# pi3_hat.net
KiCad netlist of a schematic drawn in EAGLE
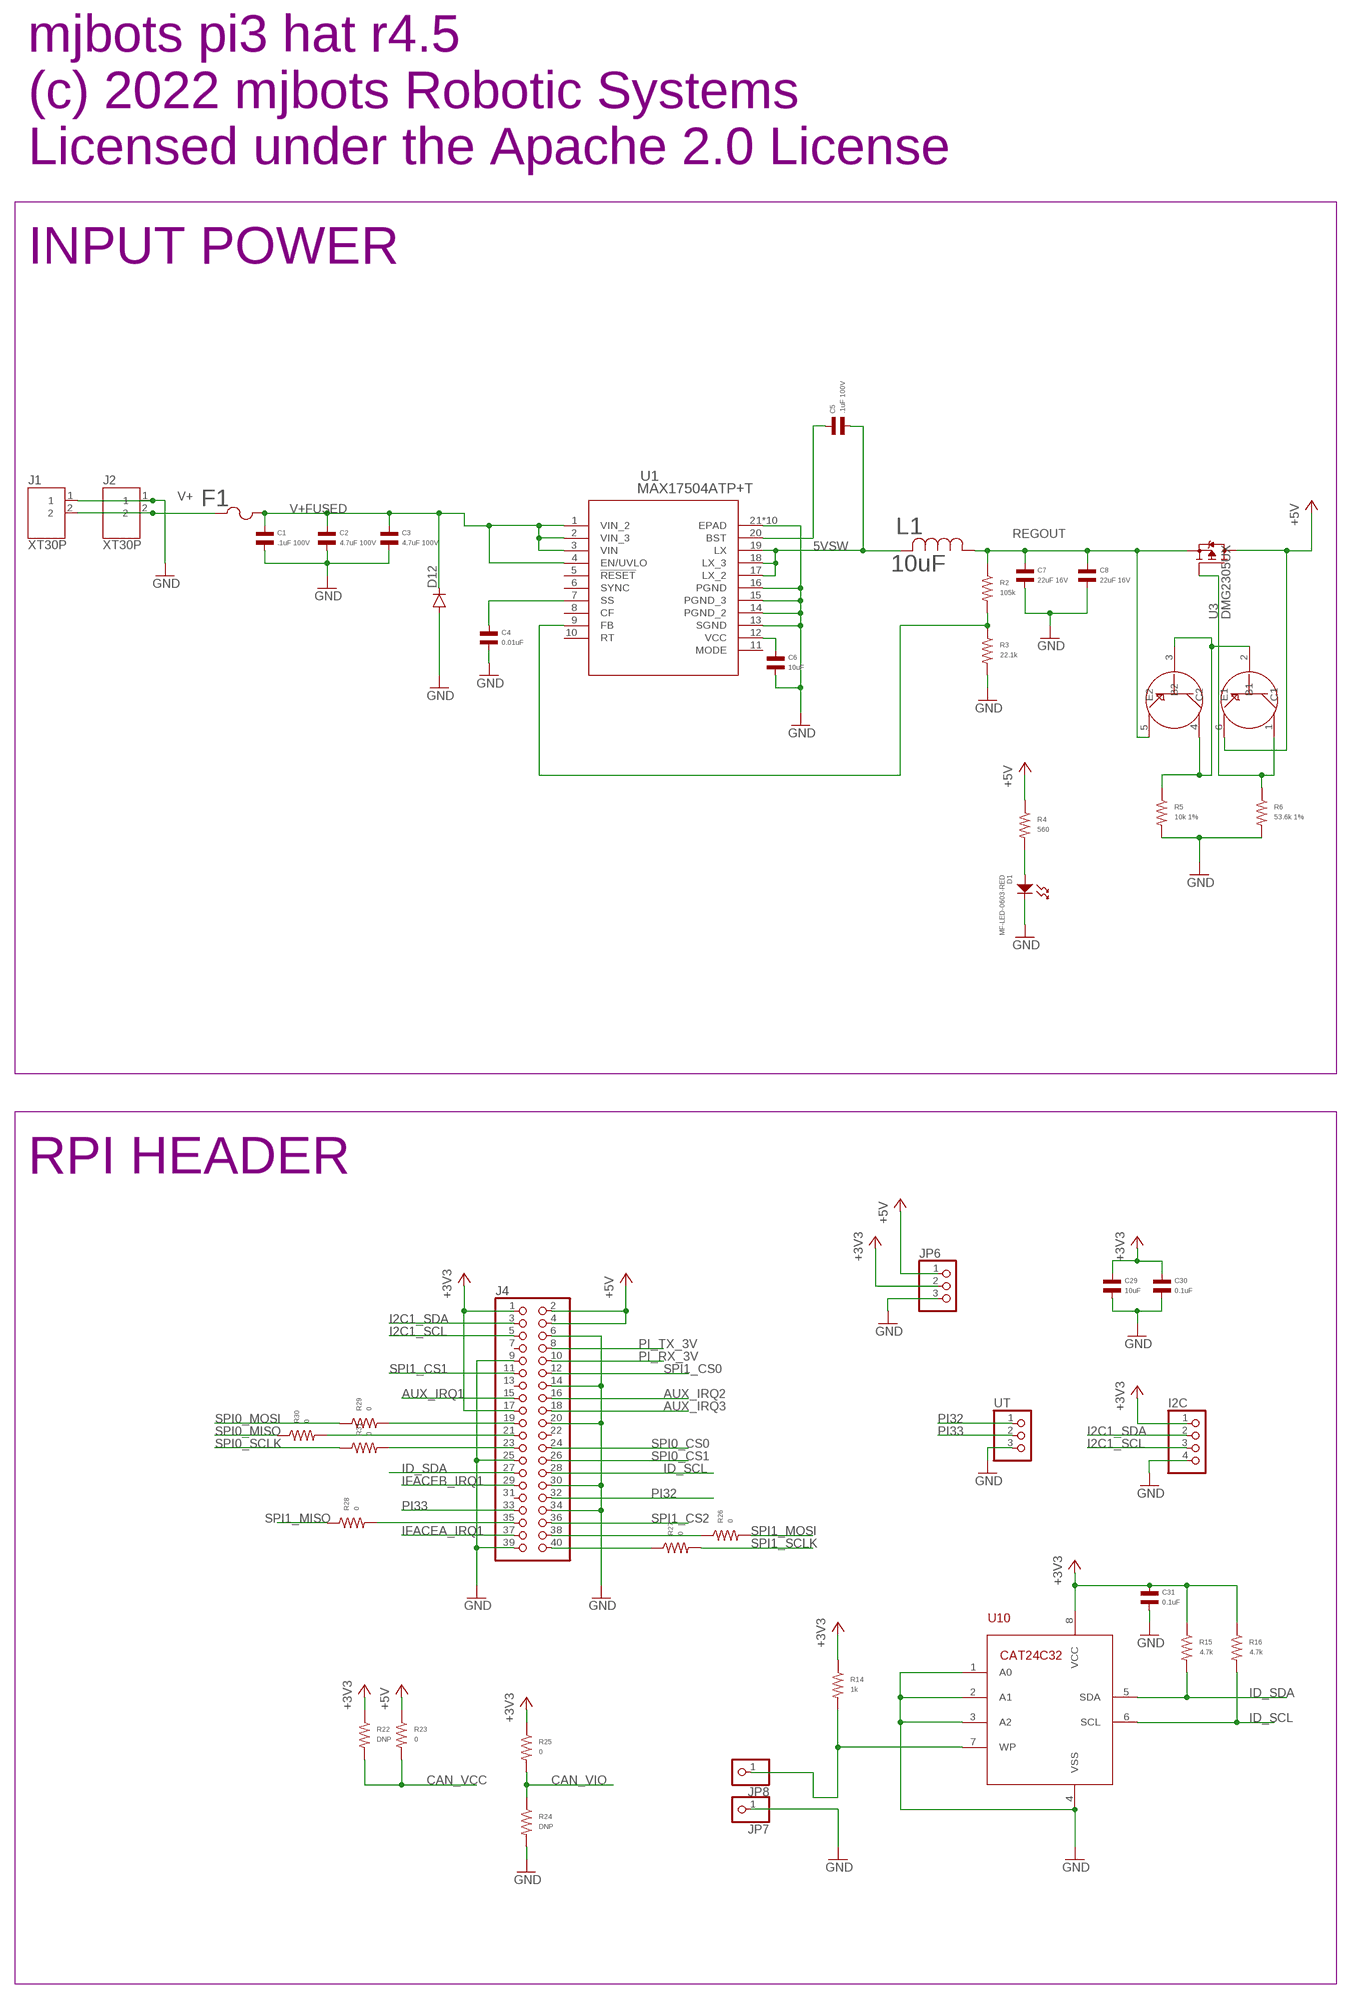
[diagram p0: schematic, sheet 1, part 1 of 3]
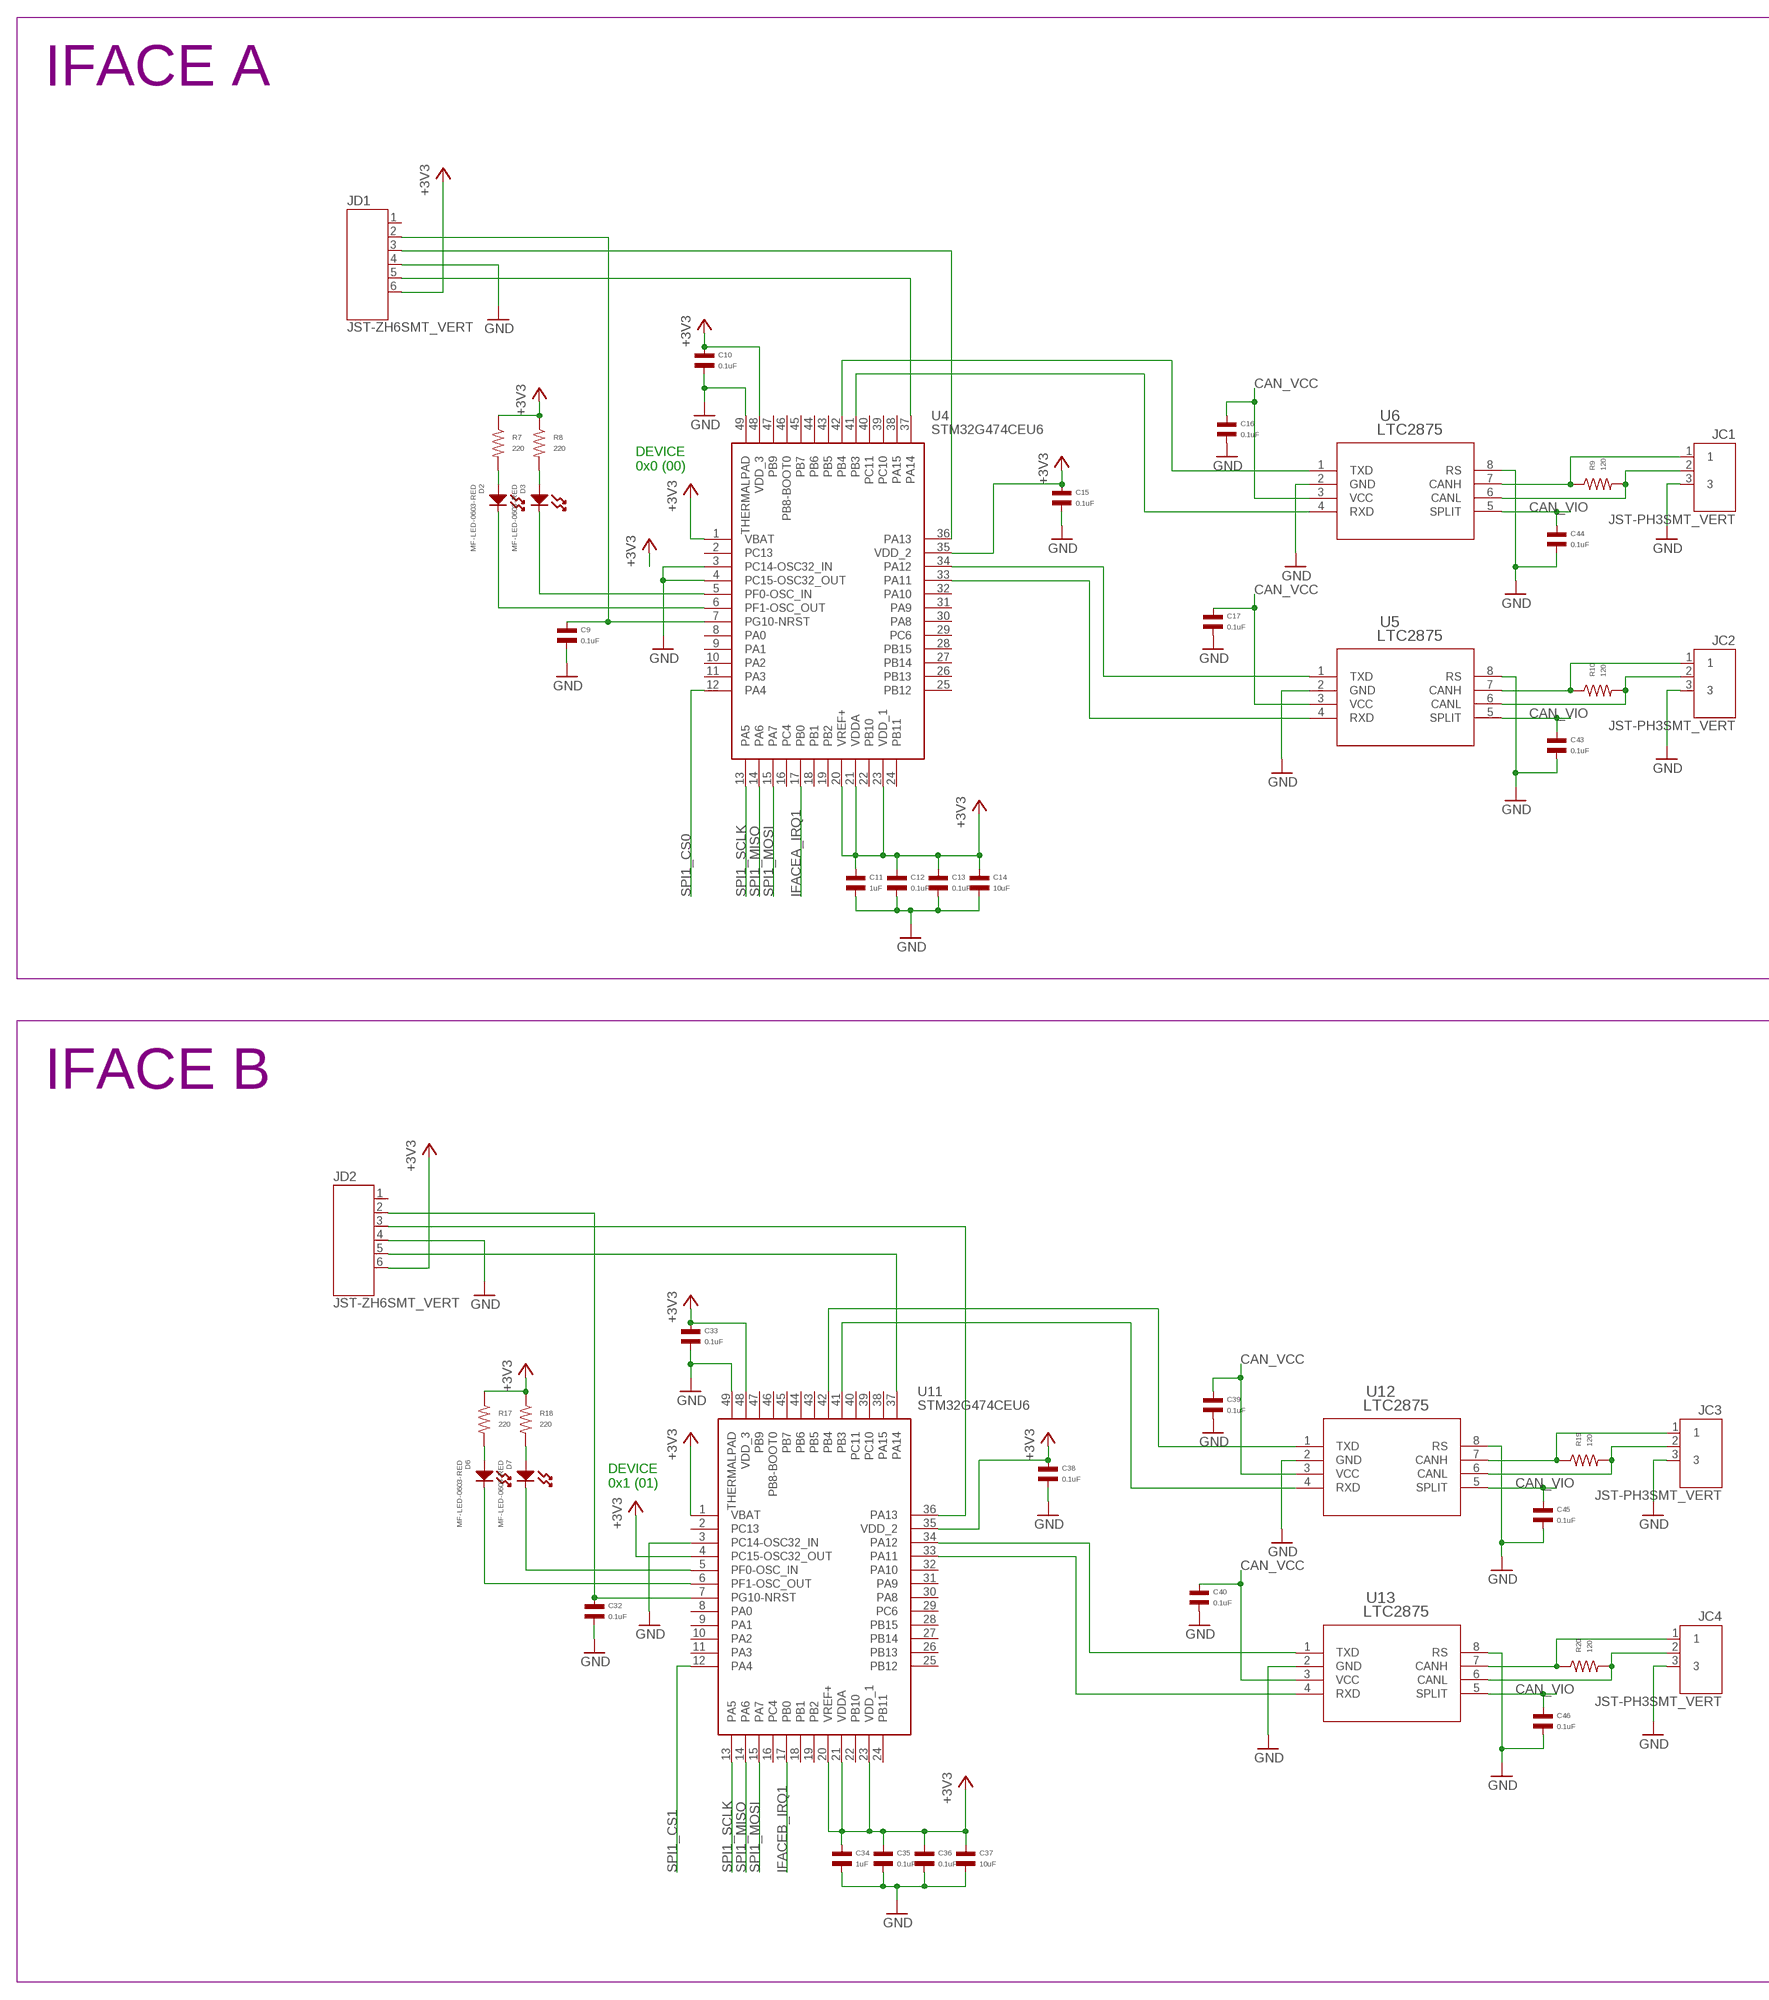
[diagram p1: schematic, sheet 1, part 2 of 3]
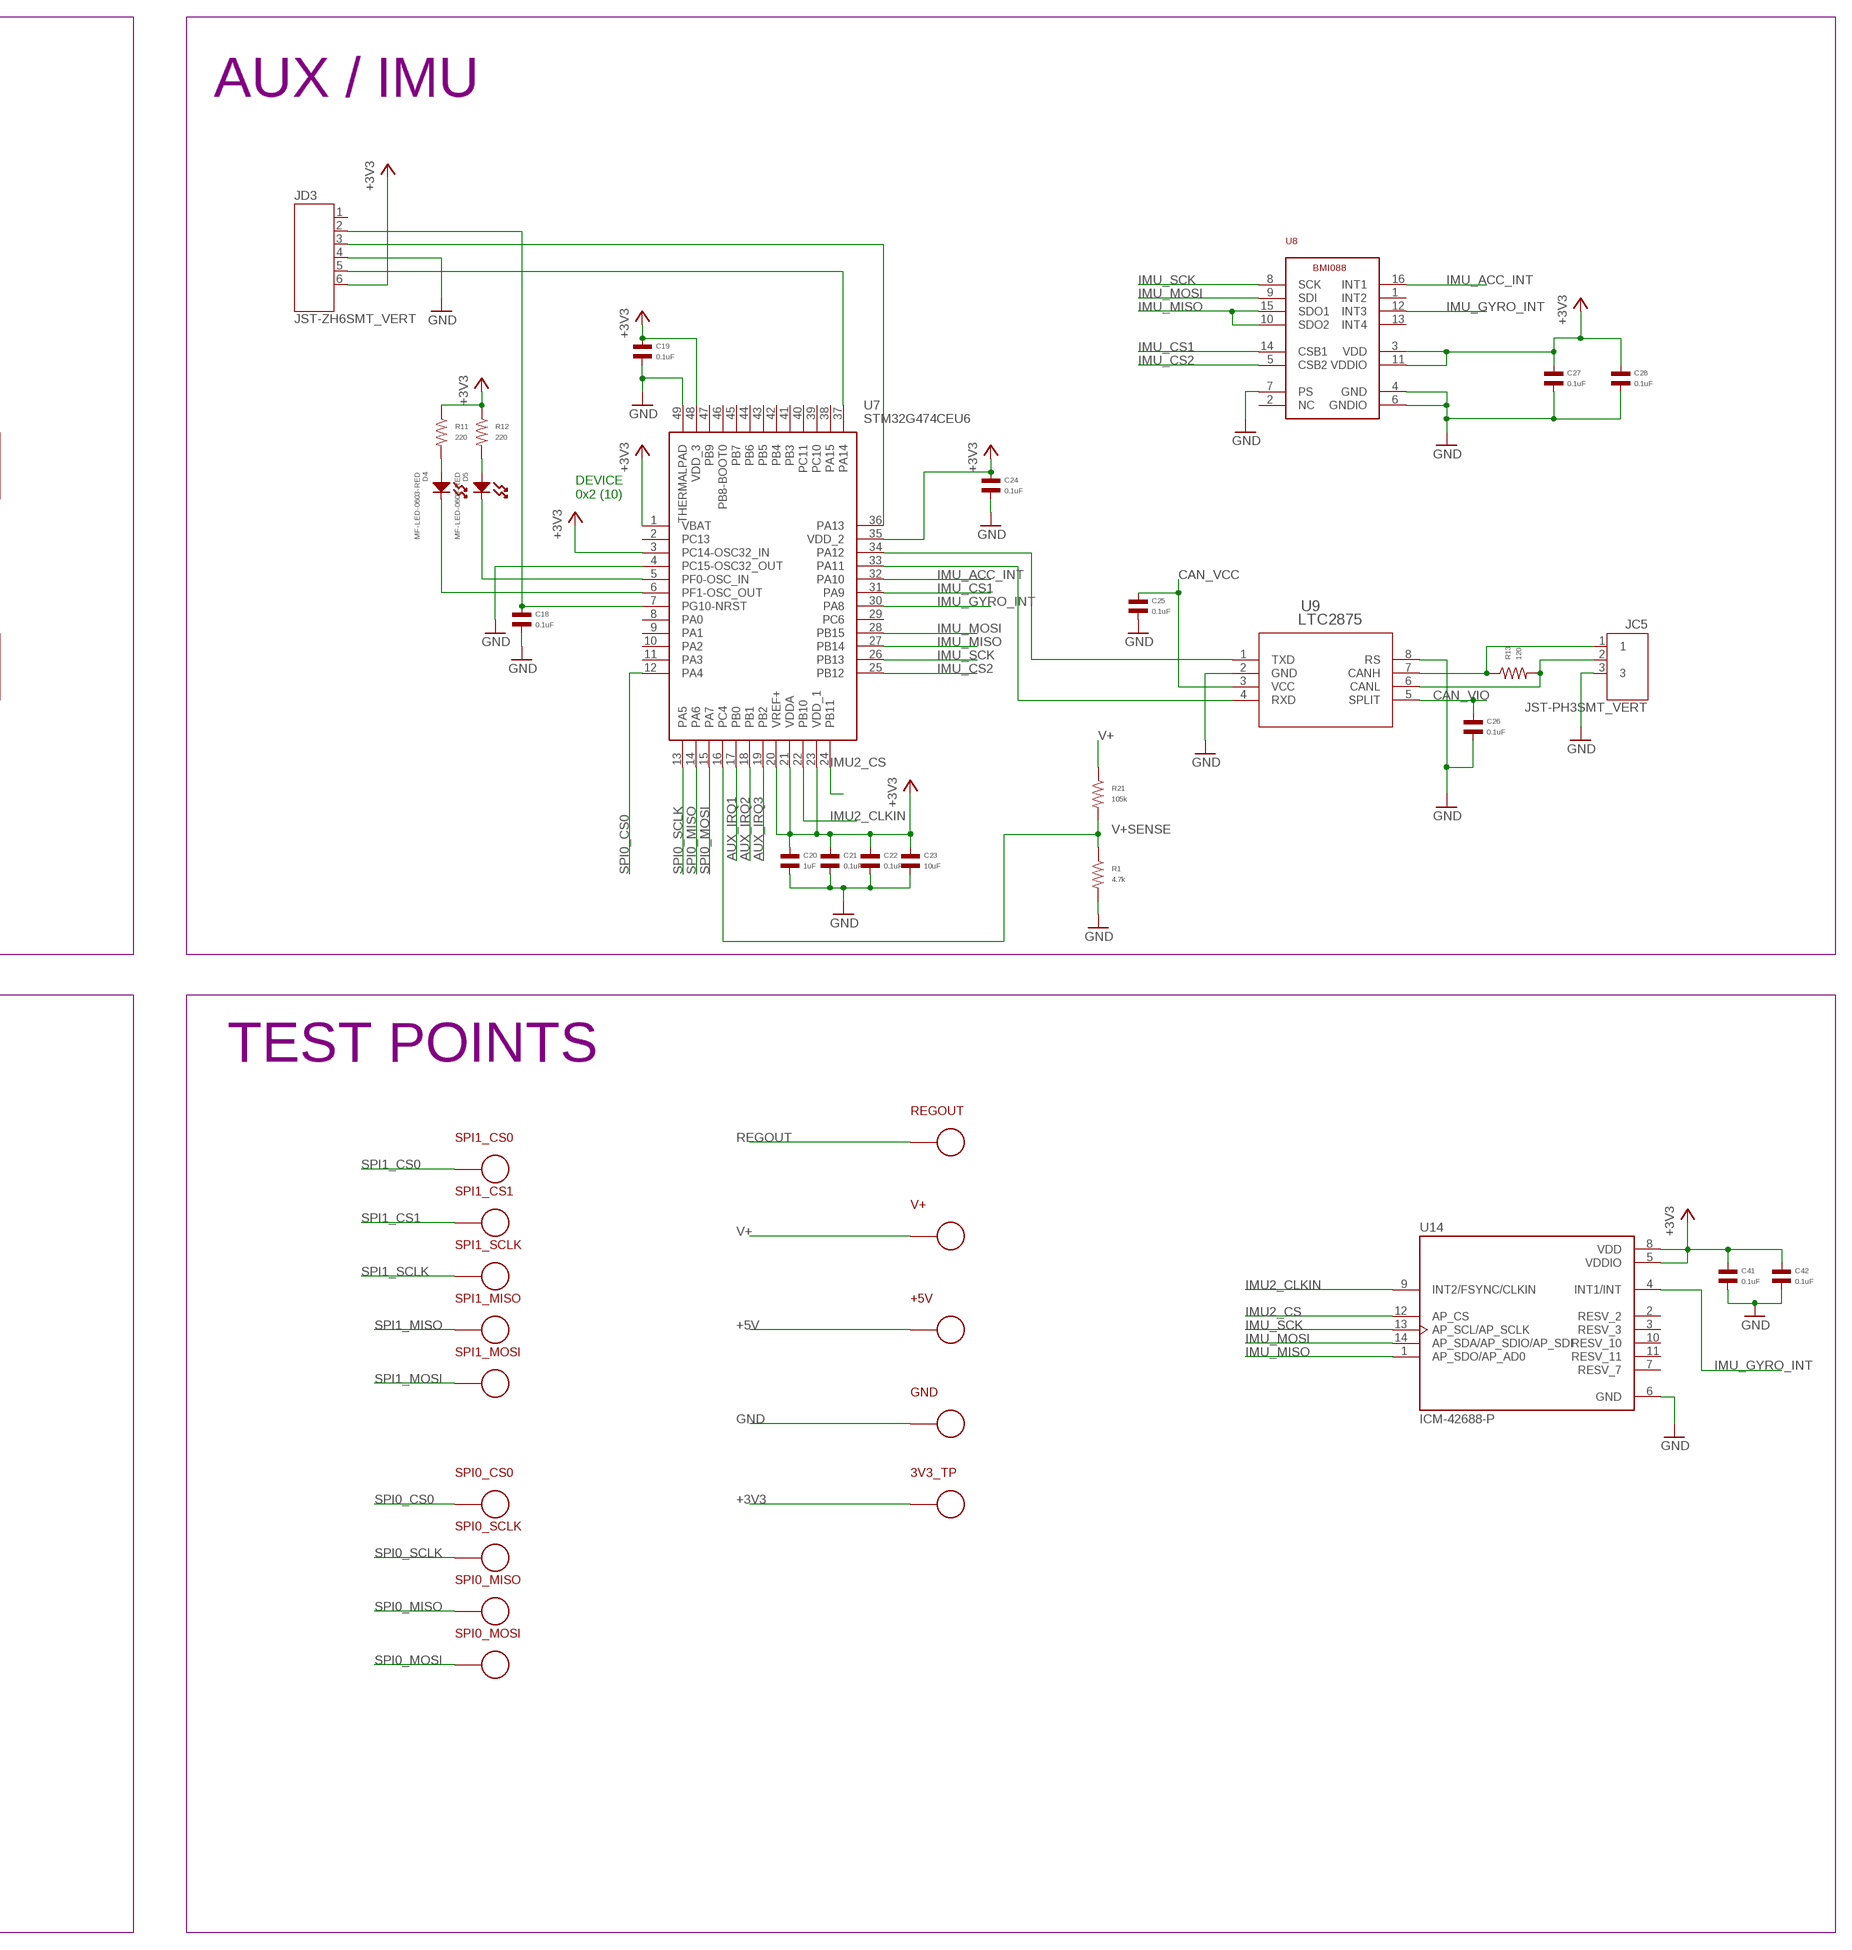
[diagram p2: schematic, sheet 1, part 3 of 3]

(export (version "E")
  (design (tool "Eeschema 10.0.6"))
  (components
    (comp (ref "+5V")
      (value "PAD24AWG_PAD")
      (footprint "eagle-import:24AWG_PAD")
      (libsource (lib "eagle-import") (part "PAD24AWG_PAD"))
    )
    (comp (ref "3V3_TP")
      (value "PAD24AWG_PAD")
      (footprint "eagle-import:24AWG_PAD")
      (libsource (lib "eagle-import") (part "PAD24AWG_PAD"))
    )
    (comp (ref "C1")
      (value ".1uF 100V")
      (footprint "eagle-import:C0805")
      (fields
        (field (name "HOUSEPART") "0")
        (field (name "MF") "KYOCERA")
        (field (name "MPN") "08051C104KAZ2A")
      )
      (libsource (lib "eagle-import") (part "CAPACITOR_NP_0805"))
    )
    (comp (ref "C2")
      (value "4.7uF 100V")
      (footprint "eagle-import:C1206")
      (fields (field (name "MF") "MURATA") (field (name "MPN") "GRJ31CC72A475KE01K"))
      (libsource (lib "eagle-import") (part "CAPACITOR_NP_1206"))
    )
    (comp (ref "C3")
      (value "4.7uF 100V")
      (footprint "eagle-import:C1206")
      (fields (field (name "MF") "MURATA") (field (name "MPN") "GRJ31CC72A475KE01K"))
      (libsource (lib "eagle-import") (part "CAPACITOR_NP_1206"))
    )
    (comp (ref "C4")
      (value "0.01uF")
      (footprint "eagle-import:C0603")
      (fields (field (name "MPN") "MF-CAP-0603-0.01uF"))
      (libsource (lib "eagle-import") (part "CAPACITOR_NP_0603"))
    )
    (comp (ref "C5")
      (value ".1uF 100V")
      (footprint "eagle-import:C0805")
      (fields
        (field (name "HOUSEPART") "0")
        (field (name "MF") "KYOCERA")
        (field (name "MPN") "08051C104KAZ2A")
      )
      (libsource (lib "eagle-import") (part "CAPACITOR_NP_0805"))
    )
    (comp (ref "C6")
      (value "10uF")
      (footprint "eagle-import:C1206")
      (fields (field (name "HOUSEPART") "YES") (field (name "MPN") "MF-CAP-1206-10uF"))
      (libsource (lib "eagle-import") (part "CAPACITOR_NP_1206"))
    )
    (comp (ref "C7")
      (value "22uF 16V")
      (footprint "eagle-import:C1210")
      (fields (field (name "MF") "SAMSUNG") (field (name "MPN") "CL32A226KOJNNNE"))
      (libsource (lib "eagle-import") (part "CAPACITOR_NP_1210"))
    )
    (comp (ref "C8")
      (value "22uF 16V")
      (footprint "eagle-import:C1210")
      (fields (field (name "MF") "SAMSUNG") (field (name "MPN") "CL32A226KOJNNNE"))
      (libsource (lib "eagle-import") (part "CAPACITOR_NP_1210"))
    )
    (comp (ref "C9")
      (value "0.1uF")
      (footprint "eagle-import:C0402")
      (fields (field (name "HOUSEPART") "YES") (field (name "MPN") "MF-CAP-0402-0.1uF"))
      (libsource (lib "eagle-import") (part "CAPACITOR_NP_0402"))
    )
    (comp (ref "C10")
      (value "0.1uF")
      (footprint "eagle-import:C0402")
      (fields (field (name "HOUSEPART") "YES") (field (name "MPN") "MF-CAP-0402-0.1uF"))
      (libsource (lib "eagle-import") (part "CAPACITOR_NP_0402"))
    )
    (comp (ref "C11")
      (value "1uF")
      (footprint "eagle-import:C0402")
      (fields (field (name "HOUSEPART") "YES") (field (name "MPN") "MF-CAP-0402-1uF"))
      (libsource (lib "eagle-import") (part "CAPACITOR_NP_0402"))
    )
    (comp (ref "C12")
      (value "0.1uF")
      (footprint "eagle-import:C0402")
      (fields (field (name "HOUSEPART") "YES") (field (name "MPN") "MF-CAP-0402-0.1uF"))
      (libsource (lib "eagle-import") (part "CAPACITOR_NP_0402"))
    )
    (comp (ref "C13")
      (value "0.1uF")
      (footprint "eagle-import:C0402")
      (fields (field (name "HOUSEPART") "YES") (field (name "MPN") "MF-CAP-0402-0.1uF"))
      (libsource (lib "eagle-import") (part "CAPACITOR_NP_0402"))
    )
    (comp (ref "C14")
      (value "10uF")
      (footprint "eagle-import:C1206")
      (fields (field (name "HOUSEPART") "YES") (field (name "MPN") "MF-CAP-1206-10uF"))
      (libsource (lib "eagle-import") (part "CAPACITOR_NP_1206"))
    )
    (comp (ref "C15")
      (value "0.1uF")
      (footprint "eagle-import:C0402")
      (fields (field (name "HOUSEPART") "YES") (field (name "MPN") "MF-CAP-0402-0.1uF"))
      (libsource (lib "eagle-import") (part "CAPACITOR_NP_0402"))
    )
    (comp (ref "C16")
      (value "0.1uF")
      (footprint "eagle-import:C0402")
      (fields (field (name "HOUSEPART") "YES") (field (name "MPN") "MF-CAP-0402-0.1uF"))
      (libsource (lib "eagle-import") (part "CAPACITOR_NP_0402"))
    )
    (comp (ref "C17")
      (value "0.1uF")
      (footprint "eagle-import:C0402")
      (fields (field (name "HOUSEPART") "YES") (field (name "MPN") "MF-CAP-0402-0.1uF"))
      (libsource (lib "eagle-import") (part "CAPACITOR_NP_0402"))
    )
    (comp (ref "C18")
      (value "0.1uF")
      (footprint "eagle-import:C0402")
      (fields (field (name "HOUSEPART") "YES") (field (name "MPN") "MF-CAP-0402-0.1uF"))
      (libsource (lib "eagle-import") (part "CAPACITOR_NP_0402"))
    )
    (comp (ref "C19")
      (value "0.1uF")
      (footprint "eagle-import:C0402")
      (fields (field (name "HOUSEPART") "YES") (field (name "MPN") "MF-CAP-0402-0.1uF"))
      (libsource (lib "eagle-import") (part "CAPACITOR_NP_0402"))
    )
    (comp (ref "C20")
      (value "1uF")
      (footprint "eagle-import:C0402")
      (fields (field (name "HOUSEPART") "YES") (field (name "MPN") "MF-CAP-0402-1uF"))
      (libsource (lib "eagle-import") (part "CAPACITOR_NP_0402"))
    )
    (comp (ref "C21")
      (value "0.1uF")
      (footprint "eagle-import:C0402")
      (fields (field (name "HOUSEPART") "YES") (field (name "MPN") "MF-CAP-0402-0.1uF"))
      (libsource (lib "eagle-import") (part "CAPACITOR_NP_0402"))
    )
    (comp (ref "C22")
      (value "0.1uF")
      (footprint "eagle-import:C0402")
      (fields (field (name "HOUSEPART") "YES") (field (name "MPN") "MF-CAP-0402-0.1uF"))
      (libsource (lib "eagle-import") (part "CAPACITOR_NP_0402"))
    )
    (comp (ref "C23")
      (value "10uF")
      (footprint "eagle-import:C1206")
      (fields (field (name "HOUSEPART") "YES") (field (name "MPN") "MF-CAP-1206-10uF"))
      (libsource (lib "eagle-import") (part "CAPACITOR_NP_1206"))
    )
    (comp (ref "C24")
      (value "0.1uF")
      (footprint "eagle-import:C0402")
      (fields (field (name "HOUSEPART") "YES") (field (name "MPN") "MF-CAP-0402-0.1uF"))
      (libsource (lib "eagle-import") (part "CAPACITOR_NP_0402"))
    )
    (comp (ref "C25")
      (value "0.1uF")
      (footprint "eagle-import:C0402")
      (fields (field (name "HOUSEPART") "YES") (field (name "MPN") "MF-CAP-0402-0.1uF"))
      (libsource (lib "eagle-import") (part "CAPACITOR_NP_0402"))
    )
    (comp (ref "C26")
      (value "0.1uF")
      (footprint "eagle-import:C0402")
      (fields (field (name "HOUSEPART") "YES") (field (name "MPN") "MF-CAP-0402-0.1uF"))
      (libsource (lib "eagle-import") (part "CAPACITOR_NP_0402"))
    )
    (comp (ref "C27")
      (value "0.1uF")
      (footprint "eagle-import:C0402")
      (fields (field (name "HOUSEPART") "YES") (field (name "MPN") "MF-CAP-0402-0.1uF"))
      (libsource (lib "eagle-import") (part "CAPACITOR_NP_0402"))
    )
    (comp (ref "C28")
      (value "0.1uF")
      (footprint "eagle-import:C0402")
      (fields (field (name "HOUSEPART") "YES") (field (name "MPN") "MF-CAP-0402-0.1uF"))
      (libsource (lib "eagle-import") (part "CAPACITOR_NP_0402"))
    )
    (comp (ref "C29")
      (value "10uF")
      (footprint "eagle-import:C1206")
      (fields (field (name "HOUSEPART") "YES") (field (name "MPN") "MF-CAP-1206-10uF"))
      (libsource (lib "eagle-import") (part "CAPACITOR_NP_1206"))
    )
    (comp (ref "C30")
      (value "0.1uF")
      (footprint "eagle-import:C0402")
      (fields (field (name "HOUSEPART") "YES") (field (name "MPN") "MF-CAP-0402-0.1uF"))
      (libsource (lib "eagle-import") (part "CAPACITOR_NP_0402"))
    )
    (comp (ref "C31")
      (value "0.1uF")
      (footprint "eagle-import:C0402")
      (fields (field (name "HOUSEPART") "YES") (field (name "MPN") "MF-CAP-0402-0.1uF"))
      (libsource (lib "eagle-import") (part "CAPACITOR_NP_0402"))
    )
    (comp (ref "C32")
      (value "0.1uF")
      (footprint "eagle-import:C0402")
      (fields (field (name "HOUSEPART") "YES") (field (name "MPN") "MF-CAP-0402-0.1uF"))
      (libsource (lib "eagle-import") (part "CAPACITOR_NP_0402"))
    )
    (comp (ref "C33")
      (value "0.1uF")
      (footprint "eagle-import:C0402")
      (fields (field (name "HOUSEPART") "YES") (field (name "MPN") "MF-CAP-0402-0.1uF"))
      (libsource (lib "eagle-import") (part "CAPACITOR_NP_0402"))
    )
    (comp (ref "C34")
      (value "1uF")
      (footprint "eagle-import:C0402")
      (fields (field (name "HOUSEPART") "YES") (field (name "MPN") "MF-CAP-0402-1uF"))
      (libsource (lib "eagle-import") (part "CAPACITOR_NP_0402"))
    )
    (comp (ref "C35")
      (value "0.1uF")
      (footprint "eagle-import:C0402")
      (fields (field (name "HOUSEPART") "YES") (field (name "MPN") "MF-CAP-0402-0.1uF"))
      (libsource (lib "eagle-import") (part "CAPACITOR_NP_0402"))
    )
    (comp (ref "C36")
      (value "0.1uF")
      (footprint "eagle-import:C0402")
      (fields (field (name "HOUSEPART") "YES") (field (name "MPN") "MF-CAP-0402-0.1uF"))
      (libsource (lib "eagle-import") (part "CAPACITOR_NP_0402"))
    )
    (comp (ref "C37")
      (value "10uF")
      (footprint "eagle-import:C1206")
      (fields (field (name "HOUSEPART") "YES") (field (name "MPN") "MF-CAP-1206-10uF"))
      (libsource (lib "eagle-import") (part "CAPACITOR_NP_1206"))
    )
    (comp (ref "C38")
      (value "0.1uF")
      (footprint "eagle-import:C0402")
      (fields (field (name "HOUSEPART") "YES") (field (name "MPN") "MF-CAP-0402-0.1uF"))
      (libsource (lib "eagle-import") (part "CAPACITOR_NP_0402"))
    )
    (comp (ref "C39")
      (value "0.1uF")
      (footprint "eagle-import:C0402")
      (fields (field (name "HOUSEPART") "YES") (field (name "MPN") "MF-CAP-0402-0.1uF"))
      (libsource (lib "eagle-import") (part "CAPACITOR_NP_0402"))
    )
    (comp (ref "C40")
      (value "0.1uF")
      (footprint "eagle-import:C0402")
      (fields (field (name "HOUSEPART") "YES") (field (name "MPN") "MF-CAP-0402-0.1uF"))
      (libsource (lib "eagle-import") (part "CAPACITOR_NP_0402"))
    )
    (comp (ref "C41")
      (value "0.1uF")
      (footprint "eagle-import:C0402")
      (fields (field (name "HOUSEPART") "YES") (field (name "MPN") "MF-CAP-0402-0.1uF"))
      (libsource (lib "eagle-import") (part "CAPACITOR_NP_0402"))
    )
    (comp (ref "C42")
      (value "0.1uF")
      (footprint "eagle-import:C0402")
      (fields (field (name "HOUSEPART") "YES") (field (name "MPN") "MF-CAP-0402-0.1uF"))
      (libsource (lib "eagle-import") (part "CAPACITOR_NP_0402"))
    )
    (comp (ref "C43")
      (value "0.1uF")
      (footprint "eagle-import:C0402")
      (fields (field (name "HOUSEPART") "YES") (field (name "MPN") "MF-CAP-0402-0.1uF"))
      (libsource (lib "eagle-import") (part "CAPACITOR_NP_0402"))
    )
    (comp (ref "C44")
      (value "0.1uF")
      (footprint "eagle-import:C0402")
      (fields (field (name "HOUSEPART") "YES") (field (name "MPN") "MF-CAP-0402-0.1uF"))
      (libsource (lib "eagle-import") (part "CAPACITOR_NP_0402"))
    )
    (comp (ref "C45")
      (value "0.1uF")
      (footprint "eagle-import:C0402")
      (fields (field (name "HOUSEPART") "YES") (field (name "MPN") "MF-CAP-0402-0.1uF"))
      (libsource (lib "eagle-import") (part "CAPACITOR_NP_0402"))
    )
    (comp (ref "C46")
      (value "0.1uF")
      (footprint "eagle-import:C0402")
      (fields (field (name "HOUSEPART") "YES") (field (name "MPN") "MF-CAP-0402-0.1uF"))
      (libsource (lib "eagle-import") (part "CAPACITOR_NP_0402"))
    )
    (comp (ref "D1")
      (value "MF-LED-0603-RED")
      (footprint "eagle-import:LED0603")
      (fields (field (name "HOUSEPART") "YES"))
      (libsource (lib "eagle-import") (part "LED_SINGLE-0603-RED"))
    )
    (comp (ref "D2")
      (value "MF-LED-0603-RED")
      (footprint "eagle-import:LED0603")
      (fields (field (name "HOUSEPART") "YES"))
      (libsource (lib "eagle-import") (part "LED_SINGLE-0603-RED"))
    )
    (comp (ref "D3")
      (value "MF-LED-0603-RED")
      (footprint "eagle-import:LED0603")
      (fields (field (name "HOUSEPART") "YES") (field (name "MPN") "MF-LED-0603-GREEN"))
      (libsource (lib "eagle-import") (part "LED_SINGLE-0603-RED"))
    )
    (comp (ref "D4")
      (value "MF-LED-0603-RED")
      (footprint "eagle-import:LED0603")
      (fields (field (name "HOUSEPART") "YES"))
      (libsource (lib "eagle-import") (part "LED_SINGLE-0603-RED"))
    )
    (comp (ref "D5")
      (value "MF-LED-0603-RED")
      (footprint "eagle-import:LED0603")
      (fields (field (name "HOUSEPART") "YES") (field (name "MPN") "MF-LED-0603-GREEN"))
      (libsource (lib "eagle-import") (part "LED_SINGLE-0603-RED"))
    )
    (comp (ref "D6")
      (value "MF-LED-0603-RED")
      (footprint "eagle-import:LED0603")
      (fields (field (name "HOUSEPART") "YES"))
      (libsource (lib "eagle-import") (part "LED_SINGLE-0603-RED"))
    )
    (comp (ref "D7")
      (value "MF-LED-0603-RED")
      (footprint "eagle-import:LED0603")
      (fields (field (name "HOUSEPART") "YES") (field (name "MPN") "MF-LED-0603-GREEN"))
      (libsource (lib "eagle-import") (part "LED_SINGLE-0603-RED"))
    )
    (comp (ref "D12")
      (value "DIODE-DO214AA")
      (footprint "eagle-import:DO214AA")
      (fields (field (name "MF") "LITTLEFUSE") (field (name "MPN") "SMBJ51A-13-F"))
      (libsource (lib "eagle-import") (part "DIODE-DO214AA"))
    )
    (comp (ref "F1")
      (value "MFU0603FF04000P100")
      (footprint "eagle-import:FUS_VISHAY_MFU0603")
      (fields
        (field (name "MF") "BEL FUSE")
        (field (name "MPN") "0686F4000-01")
        (field (name "VENDOR") "BEL FUSE")
      )
      (libsource (lib "eagle-import") (part "MFU0603FF04000P100"))
    )
    (comp (ref "GND")
      (value "PAD24AWG_PAD")
      (footprint "eagle-import:24AWG_PAD")
      (libsource (lib "eagle-import") (part "PAD24AWG_PAD"))
    )
    (comp (ref "I2C")
      (value "PINHD-1X4")
      (footprint "eagle-import:1X04")
      (fields (field (name "MF") "MacroFab") (field (name "MPN") "MF-CON-2.54mm-01x04"))
      (libsource (lib "eagle-import") (part "PINHD-1X4"))
    )
    (comp (ref "J1")
      (value "XT30P")
      (footprint "eagle-import:XT30P")
      (fields (field (name "MF") "AMASS") (field (name "MPN") "XT30UPB-M"))
      (libsource (lib "eagle-import") (part "XT30P"))
    )
    (comp (ref "J2")
      (value "XT30P")
      (footprint "eagle-import:XT30P")
      (fields (field (name "MF") "AMASS") (field (name "MPN") "XT30UPB-M"))
      (libsource (lib "eagle-import") (part "XT30P"))
    )
    (comp (ref "J4")
      (value "PI3_HEADER2X20-FLIP")
      (footprint "eagle-import:2X20FLIP")
      (fields (field (name "MF") "SULLINS") (field (name "MPN") "PPPC202LFBN-RC"))
      (libsource (lib "eagle-import") (part "PI3_HEADER2X20-FLIP"))
    )
    (comp (ref "JC1")
      (value "JST-PH3SMT_VERT")
      (footprint "eagle-import:JST_B3B_PH-SM4-TB(LF)(SN)")
      (fields (field (name "MF") "JST") (field (name "MPN") "B3B-PH-SM4-TB(LF)(SN)"))
      (libsource (lib "eagle-import") (part "JST-PH3SMT_VERT"))
    )
    (comp (ref "JC2")
      (value "JST-PH3SMT_VERT")
      (footprint "eagle-import:JST_B3B_PH-SM4-TB(LF)(SN)")
      (fields (field (name "MF") "JST") (field (name "MPN") "B3B-PH-SM4-TB(LF)(SN)"))
      (libsource (lib "eagle-import") (part "JST-PH3SMT_VERT"))
    )
    (comp (ref "JC3")
      (value "JST-PH3SMT_VERT")
      (footprint "eagle-import:JST_B3B_PH-SM4-TB(LF)(SN)")
      (fields (field (name "MF") "JST") (field (name "MPN") "B3B-PH-SM4-TB(LF)(SN)"))
      (libsource (lib "eagle-import") (part "JST-PH3SMT_VERT"))
    )
    (comp (ref "JC4")
      (value "JST-PH3SMT_VERT")
      (footprint "eagle-import:JST_B3B_PH-SM4-TB(LF)(SN)")
      (fields (field (name "MF") "JST") (field (name "MPN") "B3B-PH-SM4-TB(LF)(SN)"))
      (libsource (lib "eagle-import") (part "JST-PH3SMT_VERT"))
    )
    (comp (ref "JC5")
      (value "JST-PH3SMT_VERT")
      (footprint "eagle-import:JST_B3B_PH-SM4-TB(LF)(SN)")
      (fields (field (name "MF") "JST") (field (name "MPN") "B3B-PH-SM4-TB(LF)(SN)"))
      (libsource (lib "eagle-import") (part "JST-PH3SMT_VERT"))
    )
    (comp (ref "JD1")
      (value "JST-ZH6SMT_VERT")
      (footprint "eagle-import:JST_B6B-ZR-SM4-TF(LF)(SN)")
      (fields (field (name "MF") "JST") (field (name "MPN") "B6B-ZR-SM4-TF(LF)(SN)"))
      (libsource (lib "eagle-import") (part "JST-ZH6SMT_VERT"))
    )
    (comp (ref "JD2")
      (value "JST-ZH6SMT_VERT")
      (footprint "eagle-import:JST_B6B-ZR-SM4-TF(LF)(SN)")
      (fields (field (name "MF") "JST") (field (name "MPN") "B6B-ZR-SM4-TF(LF)(SN)"))
      (libsource (lib "eagle-import") (part "JST-ZH6SMT_VERT"))
    )
    (comp (ref "JD3")
      (value "JST-ZH6SMT_VERT")
      (footprint "eagle-import:JST_B6B-ZR-SM4-TF(LF)(SN)")
      (fields (field (name "MF") "JST") (field (name "MPN") "B6B-ZR-SM4-TF(LF)(SN)"))
      (libsource (lib "eagle-import") (part "JST-ZH6SMT_VERT"))
    )
    (comp (ref "JP6")
      (value "PINHD-1X3")
      (footprint "eagle-import:1X03")
      (fields (field (name "MF") "MacroFab") (field (name "MPN") "MF-CON-2.54mm-01x03"))
      (libsource (lib "eagle-import") (part "PINHD-1X3"))
    )
    (comp (ref "JP7")
      (value "PINHD-1X1")
      (footprint "eagle-import:1X01")
      (libsource (lib "eagle-import") (part "PINHD-1X1"))
    )
    (comp (ref "JP8")
      (value "PINHD-1X1")
      (footprint "eagle-import:1X01")
      (libsource (lib "eagle-import") (part "PINHD-1X1"))
    )
    (comp (ref "L1")
      (value "10uF")
      (footprint "eagle-import:IND_YUDEN_NS10165_YDN")
      (fields (field (name "MANUFACTURER_PART_NUMBER") "NS10165T100MNA"))
      (libsource (lib "eagle-import") (part "NS10165T100MNA"))
    )
    (comp (ref "R1")
      (value "4.7k")
      (footprint "eagle-import:R0402")
      (fields (field (name "HOUSEPART") "YES") (field (name "MPN") "MF-RES-0402-4.7K"))
      (libsource (lib "eagle-import") (part "RESISTOR_0402"))
    )
    (comp (ref "R2")
      (value "105k")
      (footprint "eagle-import:R0402")
      (fields (field (name "MF") "YAGEO") (field (name "MPN") "RC0402FR-07105KL"))
      (libsource (lib "eagle-import") (part "RESISTOR_0402"))
    )
    (comp (ref "R3")
      (value "22.1k")
      (footprint "eagle-import:R0402")
      (fields (field (name "MF") "YAGEO") (field (name "MPN") "RC0402FR-0722K1L"))
      (libsource (lib "eagle-import") (part "RESISTOR_0402"))
    )
    (comp (ref "R4")
      (value "560")
      (footprint "eagle-import:R0402")
      (fields (field (name "HOUSEPART") "YES") (field (name "MPN") "MF-RES-0402-560"))
      (libsource (lib "eagle-import") (part "RESISTOR_0402"))
    )
    (comp (ref "R5")
      (value "10k 1%")
      (footprint "eagle-import:R0603")
      (fields (field (name "MF") "YAGEO") (field (name "MPN") "RC0603FR-0710KL"))
      (libsource (lib "eagle-import") (part "RESISTOR_0603"))
    )
    (comp (ref "R6")
      (value "53.6k 1%")
      (footprint "eagle-import:R0603")
      (fields (field (name "MF") "YAGEO") (field (name "MPN") "RC0603FR-0753K6L"))
      (libsource (lib "eagle-import") (part "RESISTOR_0603"))
    )
    (comp (ref "R7")
      (value "220")
      (footprint "eagle-import:R0402")
      (fields (field (name "HOUSEPART") "YES") (field (name "MPN") "MF-RES-0402-220"))
      (libsource (lib "eagle-import") (part "RESISTOR_0402"))
    )
    (comp (ref "R8")
      (value "220")
      (footprint "eagle-import:R0402")
      (fields (field (name "HOUSEPART") "YES") (field (name "MPN") "MF-RES-0402-220"))
      (libsource (lib "eagle-import") (part "RESISTOR_0402"))
    )
    (comp (ref "R9")
      (value "120")
      (footprint "eagle-import:R0402")
      (fields (field (name "HOUSEPART") "0") (field (name "MPN") "RC0402FR-07120RL"))
      (libsource (lib "eagle-import") (part "RESISTOR_0402"))
    )
    (comp (ref "R10")
      (value "120")
      (footprint "eagle-import:R0402")
      (fields (field (name "HOUSEPART") "0") (field (name "MPN") "RC0402FR-07120RL"))
      (libsource (lib "eagle-import") (part "RESISTOR_0402"))
    )
    (comp (ref "R11")
      (value "220")
      (footprint "eagle-import:R0402")
      (fields (field (name "HOUSEPART") "YES") (field (name "MPN") "MF-RES-0402-220"))
      (libsource (lib "eagle-import") (part "RESISTOR_0402"))
    )
    (comp (ref "R12")
      (value "220")
      (footprint "eagle-import:R0402")
      (fields (field (name "HOUSEPART") "YES") (field (name "MPN") "MF-RES-0402-220"))
      (libsource (lib "eagle-import") (part "RESISTOR_0402"))
    )
    (comp (ref "R13")
      (value "120")
      (footprint "eagle-import:R0402")
      (fields (field (name "HOUSEPART") "0") (field (name "MPN") "RC0402FR-07120RL"))
      (libsource (lib "eagle-import") (part "RESISTOR_0402"))
    )
    (comp (ref "R14")
      (value "1k")
      (footprint "eagle-import:R0402")
      (fields (field (name "HOUSEPART") "YES") (field (name "MPN") "MF-RES-0402-1K"))
      (libsource (lib "eagle-import") (part "RESISTOR_0402"))
    )
    (comp (ref "R15")
      (value "4.7k")
      (footprint "eagle-import:R0402")
      (fields (field (name "HOUSEPART") "YES") (field (name "MPN") "MF-RES-0402-4.7K"))
      (libsource (lib "eagle-import") (part "RESISTOR_0402"))
    )
    (comp (ref "R16")
      (value "4.7k")
      (footprint "eagle-import:R0402")
      (fields (field (name "HOUSEPART") "YES") (field (name "MPN") "MF-RES-0402-4.7K"))
      (libsource (lib "eagle-import") (part "RESISTOR_0402"))
    )
    (comp (ref "R17")
      (value "220")
      (footprint "eagle-import:R0402")
      (fields (field (name "HOUSEPART") "YES") (field (name "MPN") "MF-RES-0402-220"))
      (libsource (lib "eagle-import") (part "RESISTOR_0402"))
    )
    (comp (ref "R18")
      (value "220")
      (footprint "eagle-import:R0402")
      (fields (field (name "HOUSEPART") "YES") (field (name "MPN") "MF-RES-0402-220"))
      (libsource (lib "eagle-import") (part "RESISTOR_0402"))
    )
    (comp (ref "R19")
      (value "120")
      (footprint "eagle-import:R0402")
      (fields (field (name "HOUSEPART") "0") (field (name "MPN") "RC0402FR-07120RL"))
      (libsource (lib "eagle-import") (part "RESISTOR_0402"))
    )
    (comp (ref "R20")
      (value "120")
      (footprint "eagle-import:R0402")
      (fields (field (name "HOUSEPART") "0") (field (name "MPN") "RC0402FR-07120RL"))
      (libsource (lib "eagle-import") (part "RESISTOR_0402"))
    )
    (comp (ref "R21")
      (value "105k")
      (footprint "eagle-import:R0402")
      (fields (field (name "MF") "YAGEO") (field (name "MPN") "RC0402FR-07105KL"))
      (libsource (lib "eagle-import") (part "RESISTOR_0402"))
    )
    (comp (ref "R22")
      (value "DNP")
      (footprint "eagle-import:R0402")
      (fields
        (field (name "HOUSEPART") "YES")
        (field (name "MPN") "MF-RES-0402-0")
        (field (name "POPULATE") "0")
      )
      (libsource (lib "eagle-import") (part "RESISTOR_0402"))
    )
    (comp (ref "R23")
      (value "0")
      (footprint "eagle-import:R0402")
      (fields (field (name "HOUSEPART") "YES") (field (name "MPN") "MF-RES-0402-0"))
      (libsource (lib "eagle-import") (part "RESISTOR_0402"))
    )
    (comp (ref "R24")
      (value "DNP")
      (footprint "eagle-import:R0402")
      (fields
        (field (name "HOUSEPART") "YES")
        (field (name "MPN") "MF-RES-0402-0")
        (field (name "POPULATE") "0")
      )
      (libsource (lib "eagle-import") (part "RESISTOR_0402"))
    )
    (comp (ref "R25")
      (value "0")
      (footprint "eagle-import:R0402")
      (fields (field (name "HOUSEPART") "YES") (field (name "MPN") "MF-RES-0402-0"))
      (libsource (lib "eagle-import") (part "RESISTOR_0402"))
    )
    (comp (ref "R26")
      (value "0")
      (footprint "eagle-import:R0402")
      (fields (field (name "HOUSEPART") "YES") (field (name "MPN") "MF-RES-0402-0"))
      (libsource (lib "eagle-import") (part "RESISTOR_0402"))
    )
    (comp (ref "R27")
      (value "0")
      (footprint "eagle-import:R0402")
      (fields (field (name "HOUSEPART") "YES") (field (name "MPN") "MF-RES-0402-0"))
      (libsource (lib "eagle-import") (part "RESISTOR_0402"))
    )
    (comp (ref "R28")
      (value "0")
      (footprint "eagle-import:R0402")
      (fields (field (name "HOUSEPART") "YES") (field (name "MPN") "MF-RES-0402-0"))
      (libsource (lib "eagle-import") (part "RESISTOR_0402"))
    )
    (comp (ref "R29")
      (value "0")
      (footprint "eagle-import:R0402")
      (fields (field (name "HOUSEPART") "YES") (field (name "MPN") "MF-RES-0402-0"))
      (libsource (lib "eagle-import") (part "RESISTOR_0402"))
    )
    (comp (ref "R30")
      (value "0")
      (footprint "eagle-import:R0402")
      (fields (field (name "HOUSEPART") "YES") (field (name "MPN") "MF-RES-0402-0"))
      (libsource (lib "eagle-import") (part "RESISTOR_0402"))
    )
    (comp (ref "R31")
      (value "0")
      (footprint "eagle-import:R0402")
      (fields (field (name "HOUSEPART") "YES") (field (name "MPN") "MF-RES-0402-0"))
      (libsource (lib "eagle-import") (part "RESISTOR_0402"))
    )
    (comp (ref "REGOUT")
      (value "PAD24AWG_PAD")
      (footprint "eagle-import:24AWG_PAD")
      (libsource (lib "eagle-import") (part "PAD24AWG_PAD"))
    )
    (comp (ref "SPI0_CS0")
      (value "PAD24AWG_PAD")
      (footprint "eagle-import:24AWG_PAD")
      (libsource (lib "eagle-import") (part "PAD24AWG_PAD"))
    )
    (comp (ref "SPI0_MISO")
      (value "PAD24AWG_PAD")
      (footprint "eagle-import:24AWG_PAD")
      (libsource (lib "eagle-import") (part "PAD24AWG_PAD"))
    )
    (comp (ref "SPI0_MOSI")
      (value "PAD24AWG_PAD")
      (footprint "eagle-import:24AWG_PAD")
      (libsource (lib "eagle-import") (part "PAD24AWG_PAD"))
    )
    (comp (ref "SPI0_SCLK")
      (value "PAD24AWG_PAD")
      (footprint "eagle-import:24AWG_PAD")
      (libsource (lib "eagle-import") (part "PAD24AWG_PAD"))
    )
    (comp (ref "SPI1_CS0")
      (value "PAD24AWG_PAD")
      (footprint "eagle-import:24AWG_PAD")
      (libsource (lib "eagle-import") (part "PAD24AWG_PAD"))
    )
    (comp (ref "SPI1_CS1")
      (value "PAD24AWG_PAD")
      (footprint "eagle-import:24AWG_PAD")
      (libsource (lib "eagle-import") (part "PAD24AWG_PAD"))
    )
    (comp (ref "SPI1_MISO")
      (value "PAD24AWG_PAD")
      (footprint "eagle-import:24AWG_PAD")
      (libsource (lib "eagle-import") (part "PAD24AWG_PAD"))
    )
    (comp (ref "SPI1_MOSI")
      (value "PAD24AWG_PAD")
      (footprint "eagle-import:24AWG_PAD")
      (libsource (lib "eagle-import") (part "PAD24AWG_PAD"))
    )
    (comp (ref "SPI1_SCLK")
      (value "PAD24AWG_PAD")
      (footprint "eagle-import:24AWG_PAD")
      (libsource (lib "eagle-import") (part "PAD24AWG_PAD"))
    )
    (comp (ref "U1")
      (value "MAX17504ATP+T")
      (footprint "eagle-import:21-0140L_T2055-4_MXM")
      (fields (field (name "COPYRIGHT") "Copyright (C) 2018 Accelerated Designs. All rights reserved"))
      (libsource (lib "eagle-import") (part "MAX17504ATP+T"))
    )
    (comp (ref "U2")
      (value "DMMT5401")
      (footprint "eagle-import:SOT26")
      (fields (field (name "MF") "Didoes Incorporated") (field (name "MPN") "DMMT5401-7-F"))
      (libsource (lib "eagle-import") (part "DMMT5401"))
    )
    (comp (ref "U3")
      (value "DMG2305UX")
      (footprint "eagle-import:SOT23")
      (fields (field (name "MF") "Alpha & Omega") (field (name "MPN") "AO3415A"))
      (libsource (lib "eagle-import") (part "DMG2305UX"))
    )
    (comp (ref "U4")
      (value "STM32G474CEU6")
      (footprint "eagle-import:QFN50P700X700X60-49N")
      (fields (field (name "MOUSER_PART_NUMBER") "511-STM32G474CEU6") (field (name "MF") "ST"))
      (libsource (lib "eagle-import") (part "STM32G474CEU6"))
    )
    (comp (ref "U5")
      (value "LTC2875")
      (footprint "eagle-import:SOIC8")
      (fields (field (name "MF") "Analog") (field (name "MPN") "TCAN1057AEVDRQ1‎"))
      (libsource (lib "eagle-import") (part "LTC2875"))
    )
    (comp (ref "U6")
      (value "LTC2875")
      (footprint "eagle-import:SOIC8")
      (fields (field (name "MF") "Analog") (field (name "MPN") "TCAN1057AEVDRQ1‎"))
      (libsource (lib "eagle-import") (part "LTC2875"))
    )
    (comp (ref "U7")
      (value "STM32G474CEU6")
      (footprint "eagle-import:QFN50P700X700X60-49N")
      (fields (field (name "MOUSER_PART_NUMBER") "511-STM32G474CEU6") (field (name "MF") "ST"))
      (libsource (lib "eagle-import") (part "STM32G474CEU6"))
    )
    (comp (ref "U8")
      (value "BMI088LGA16")
      (footprint "eagle-import:LGA16")
      (fields (field (name "MF") "BOSCH") (field (name "MPN") "BMI088"))
      (libsource (lib "eagle-import") (part "BMI088LGA16"))
    )
    (comp (ref "U9")
      (value "LTC2875")
      (footprint "eagle-import:SOIC8")
      (fields (field (name "MF") "Analog") (field (name "MPN") "TCAN1057AEVDRQ1‎"))
      (libsource (lib "eagle-import") (part "LTC2875"))
    )
    (comp (ref "U10")
      (value "CAT24C32UDFN8")
      (footprint "eagle-import:UDFN8_2X3_ONS")
      (fields (field (name "MF") "ON Semiconductor") (field (name "MPN") "CAT24C32HU4I-GT3"))
      (libsource (lib "eagle-import") (part "CAT24C32UDFN8"))
    )
    (comp (ref "U11")
      (value "STM32G474CEU6")
      (footprint "eagle-import:QFN50P700X700X60-49N")
      (fields (field (name "MOUSER_PART_NUMBER") "511-STM32G474CEU6") (field (name "MF") "ST"))
      (libsource (lib "eagle-import") (part "STM32G474CEU6"))
    )
    (comp (ref "U12")
      (value "LTC2875")
      (footprint "eagle-import:SOIC8")
      (fields (field (name "MF") "Analog") (field (name "MPN") "TCAN1057AEVDRQ1‎"))
      (libsource (lib "eagle-import") (part "LTC2875"))
    )
    (comp (ref "U13")
      (value "LTC2875")
      (footprint "eagle-import:SOIC8")
      (fields (field (name "MF") "Analog") (field (name "MPN") "TCAN1057AEVDRQ1‎"))
      (libsource (lib "eagle-import") (part "LTC2875"))
    )
    (comp (ref "U14")
      (value "ICM-42688-P")
      (footprint "eagle-import:PQFN50P300X250X97-14N")
      (fields
        (field (name "DIGI-KEY_PART_NUMBER") "1428-ICM-42688-PCT-ND")
        (field (name "MF") "TDK InvenSense")
      )
      (libsource (lib "eagle-import") (part "ICM-42688-P"))
    )
    (comp (ref "UT")
      (value "PINHD-1X3")
      (footprint "eagle-import:1X03")
      (fields (field (name "MF") "MacroFab") (field (name "MPN") "MF-CON-2.54mm-01x03"))
      (libsource (lib "eagle-import") (part "PINHD-1X3"))
    )
    (comp (ref "V+")
      (value "PAD24AWG_PAD")
      (footprint "eagle-import:24AWG_PAD")
      (libsource (lib "eagle-import") (part "PAD24AWG_PAD"))
    )
  )
  (nets
    (net (code "1") (name "+3V3") (class "Default")
      (node (ref "3V3_TP") (pin "P$1") (pinfunction "P$1_P$1") (pintype "bidirectional"))
      (node (ref "C10") (pin "P$1") (pinfunction "P$1_P$1") (pintype "passive"))
      (node (ref "C11") (pin "P$1") (pinfunction "P$1_P$1") (pintype "passive"))
      (node (ref "C12") (pin "P$1") (pinfunction "P$1_P$1") (pintype "passive"))
      (node (ref "C13") (pin "P$1") (pinfunction "P$1_P$1") (pintype "passive"))
      (node (ref "C14") (pin "P$1") (pinfunction "P$1_P$1") (pintype "passive"))
      (node (ref "C15") (pin "P$1") (pinfunction "P$1_P$1") (pintype "passive"))
      (node (ref "C19") (pin "P$1") (pinfunction "P$1_P$1") (pintype "passive"))
      (node (ref "C20") (pin "P$1") (pinfunction "P$1_P$1") (pintype "passive"))
      (node (ref "C21") (pin "P$1") (pinfunction "P$1_P$1") (pintype "passive"))
      (node (ref "C22") (pin "P$1") (pinfunction "P$1_P$1") (pintype "passive"))
      (node (ref "C23") (pin "P$1") (pinfunction "P$1_P$1") (pintype "passive"))
      (node (ref "C24") (pin "P$1") (pinfunction "P$1_P$1") (pintype "passive"))
      (node (ref "C27") (pin "P$1") (pinfunction "P$1_P$1") (pintype "passive"))
      (node (ref "C28") (pin "P$1") (pinfunction "P$1_P$1") (pintype "passive"))
      (node (ref "C29") (pin "P$1") (pinfunction "P$1_P$1") (pintype "passive"))
      (node (ref "C30") (pin "P$1") (pinfunction "P$1_P$1") (pintype "passive"))
      (node (ref "C31") (pin "P$1") (pinfunction "P$1_P$1") (pintype "passive"))
      (node (ref "C33") (pin "P$1") (pinfunction "P$1_P$1") (pintype "passive"))
      (node (ref "C34") (pin "P$1") (pinfunction "P$1_P$1") (pintype "passive"))
      (node (ref "C35") (pin "P$1") (pinfunction "P$1_P$1") (pintype "passive"))
      (node (ref "C36") (pin "P$1") (pinfunction "P$1_P$1") (pintype "passive"))
      (node (ref "C37") (pin "P$1") (pinfunction "P$1_P$1") (pintype "passive"))
      (node (ref "C38") (pin "P$1") (pinfunction "P$1_P$1") (pintype "passive"))
      (node (ref "C41") (pin "P$1") (pinfunction "P$1_P$1") (pintype "passive"))
      (node (ref "C42") (pin "P$1") (pinfunction "P$1_P$1") (pintype "passive"))
      (node (ref "I2C") (pin "1") (pinfunction "1_1") (pintype "passive"))
      (node (ref "J4") (pin "1") (pinfunction "1_1") (pintype "passive"))
      (node (ref "J4") (pin "17") (pinfunction "17_17") (pintype "passive"))
      (node (ref "JD1") (pin "6") (pinfunction "6_6") (pintype "passive"))
      (node (ref "JD2") (pin "6") (pinfunction "6_6") (pintype "passive"))
      (node (ref "JD3") (pin "6") (pinfunction "6_6") (pintype "passive"))
      (node (ref "JP6") (pin "2") (pinfunction "2_2") (pintype "passive"))
      (node (ref "R11") (pin "P$1") (pinfunction "P$1_P$1") (pintype "passive"))
      (node (ref "R12") (pin "P$1") (pinfunction "P$1_P$1") (pintype "passive"))
      (node (ref "R14") (pin "P$1") (pinfunction "P$1_P$1") (pintype "passive"))
      (node (ref "R15") (pin "P$1") (pinfunction "P$1_P$1") (pintype "passive"))
      (node (ref "R16") (pin "P$1") (pinfunction "P$1_P$1") (pintype "passive"))
      (node (ref "R17") (pin "P$1") (pinfunction "P$1_P$1") (pintype "passive"))
      (node (ref "R18") (pin "P$1") (pinfunction "P$1_P$1") (pintype "passive"))
      (node (ref "R22") (pin "P$1") (pinfunction "P$1_P$1") (pintype "passive"))
      (node (ref "R25") (pin "P$1") (pinfunction "P$1_P$1") (pintype "passive"))
      (node (ref "R7") (pin "P$1") (pinfunction "P$1_P$1") (pintype "passive"))
      (node (ref "R8") (pin "P$1") (pinfunction "P$1_P$1") (pintype "passive"))
      (node (ref "U10") (pin "8") (pinfunction "VCC_8") (pintype "bidirectional"))
      (node (ref "U11") (pin "1") (pinfunction "VBAT_1") (pintype "bidirectional"))
      (node (ref "U11") (pin "20") (pinfunction "VREF+_20") (pintype "bidirectional"))
      (node (ref "U11") (pin "21") (pinfunction "VDDA_21") (pintype "bidirectional"))
      (node (ref "U11") (pin "23") (pinfunction "VDD_1_23") (pintype "bidirectional"))
      (node (ref "U11") (pin "35") (pinfunction "VDD_2_35") (pintype "bidirectional"))
      (node (ref "U11") (pin "4") (pinfunction "PC15-OSC32_OUT_4") (pintype "bidirectional"))
      (node (ref "U11") (pin "48") (pinfunction "VDD_3_48") (pintype "bidirectional"))
      (node (ref "U14") (pin "5") (pinfunction "VDDIO_5") (pintype "power_in"))
      (node (ref "U14") (pin "8") (pinfunction "VDD_8") (pintype "power_in"))
      (node (ref "U4") (pin "1") (pinfunction "VBAT_1") (pintype "bidirectional"))
      (node (ref "U4") (pin "20") (pinfunction "VREF+_20") (pintype "bidirectional"))
      (node (ref "U4") (pin "21") (pinfunction "VDDA_21") (pintype "bidirectional"))
      (node (ref "U4") (pin "23") (pinfunction "VDD_1_23") (pintype "bidirectional"))
      (node (ref "U4") (pin "35") (pinfunction "VDD_2_35") (pintype "bidirectional"))
      (node (ref "U4") (pin "48") (pinfunction "VDD_3_48") (pintype "bidirectional"))
      (node (ref "U7") (pin "1") (pinfunction "VBAT_1") (pintype "bidirectional"))
      (node (ref "U7") (pin "20") (pinfunction "VREF+_20") (pintype "bidirectional"))
      (node (ref "U7") (pin "21") (pinfunction "VDDA_21") (pintype "bidirectional"))
      (node (ref "U7") (pin "23") (pinfunction "VDD_1_23") (pintype "bidirectional"))
      (node (ref "U7") (pin "3") (pinfunction "PC14-OSC32_IN_3") (pintype "bidirectional"))
      (node (ref "U7") (pin "35") (pinfunction "VDD_2_35") (pintype "bidirectional"))
      (node (ref "U7") (pin "48") (pinfunction "VDD_3_48") (pintype "bidirectional"))
      (node (ref "U8") (pin "11") (pinfunction "VDDIO_11") (pintype "bidirectional"))
      (node (ref "U8") (pin "3") (pinfunction "VDD_3") (pintype "bidirectional"))
    )
    (net (code "2") (name "+5V") (class "Default")
      (node (ref "+5V") (pin "P$1") (pinfunction "P$1_P$1") (pintype "bidirectional"))
      (node (ref "J4") (pin "2") (pinfunction "2_2") (pintype "passive"))
      (node (ref "J4") (pin "4") (pinfunction "4_4") (pintype "passive"))
      (node (ref "JP6") (pin "1") (pinfunction "1_1") (pintype "passive"))
      (node (ref "R23") (pin "P$1") (pinfunction "P$1_P$1") (pintype "passive"))
      (node (ref "R4") (pin "P$1") (pinfunction "P$1_P$1") (pintype "passive"))
      (node (ref "U2") (pin "6") (pinfunction "E1_6") (pintype "bidirectional"))
      (node (ref "U3") (pin "3") (pinfunction "D_3") (pintype "passive"))
    )
    (net (code "3") (name "/5VSW") (class "Default")
      (node (ref "C5") (pin "P$2") (pinfunction "P$2_P$2") (pintype "passive"))
      (node (ref "L1") (pin "2") (pinfunction "2_2") (pintype "passive"))
      (node (ref "U1") (pin "17") (pinfunction "LX_2_17") (pintype "passive"))
      (node (ref "U1") (pin "18") (pinfunction "LX_3_18") (pintype "passive"))
      (node (ref "U1") (pin "19") (pinfunction "LX_19") (pintype "passive"))
    )
    (net (code "4") (name "/AUX_IRQ1") (class "Default")
      (node (ref "J4") (pin "15") (pinfunction "15_15") (pintype "passive"))
      (node (ref "U7") (pin "17") (pinfunction "PB0_17") (pintype "bidirectional"))
    )
    (net (code "5") (name "/AUX_IRQ2") (class "Default")
      (node (ref "J4") (pin "16") (pinfunction "16_16") (pintype "passive"))
      (node (ref "U7") (pin "18") (pinfunction "PB1_18") (pintype "bidirectional"))
    )
    (net (code "6") (name "/AUX_IRQ3") (class "Default")
      (node (ref "J4") (pin "18") (pinfunction "18_18") (pintype "passive"))
      (node (ref "U7") (pin "19") (pinfunction "PB2_19") (pintype "bidirectional"))
    )
    (net (code "7") (name "/CAN_VCC") (class "Default")
      (node (ref "C16") (pin "P$1") (pinfunction "P$1_P$1") (pintype "passive"))
      (node (ref "C17") (pin "P$1") (pinfunction "P$1_P$1") (pintype "passive"))
      (node (ref "C25") (pin "P$1") (pinfunction "P$1_P$1") (pintype "passive"))
      (node (ref "C39") (pin "P$1") (pinfunction "P$1_P$1") (pintype "passive"))
      (node (ref "C40") (pin "P$1") (pinfunction "P$1_P$1") (pintype "passive"))
      (node (ref "R22") (pin "P$2") (pinfunction "P$2_P$2") (pintype "passive"))
      (node (ref "R23") (pin "P$2") (pinfunction "P$2_P$2") (pintype "passive"))
      (node (ref "U12") (pin "3") (pinfunction "VCC_3") (pintype "power_in"))
      (node (ref "U13") (pin "3") (pinfunction "VCC_3") (pintype "power_in"))
      (node (ref "U5") (pin "3") (pinfunction "VCC_3") (pintype "power_in"))
      (node (ref "U6") (pin "3") (pinfunction "VCC_3") (pintype "power_in"))
      (node (ref "U9") (pin "3") (pinfunction "VCC_3") (pintype "power_in"))
    )
    (net (code "8") (name "/CAN_VIO") (class "Default")
      (node (ref "C26") (pin "P$1") (pinfunction "P$1_P$1") (pintype "passive"))
      (node (ref "C43") (pin "P$1") (pinfunction "P$1_P$1") (pintype "passive"))
      (node (ref "C44") (pin "P$1") (pinfunction "P$1_P$1") (pintype "passive"))
      (node (ref "C45") (pin "P$1") (pinfunction "P$1_P$1") (pintype "passive"))
      (node (ref "C46") (pin "P$1") (pinfunction "P$1_P$1") (pintype "passive"))
      (node (ref "R24") (pin "P$1") (pinfunction "P$1_P$1") (pintype "passive"))
      (node (ref "R25") (pin "P$2") (pinfunction "P$2_P$2") (pintype "passive"))
      (node (ref "U12") (pin "5") (pinfunction "SPLIT_5") (pintype "input"))
      (node (ref "U13") (pin "5") (pinfunction "SPLIT_5") (pintype "input"))
      (node (ref "U5") (pin "5") (pinfunction "SPLIT_5") (pintype "input"))
      (node (ref "U6") (pin "5") (pinfunction "SPLIT_5") (pintype "input"))
      (node (ref "U9") (pin "5") (pinfunction "SPLIT_5") (pintype "input"))
    )
    (net (code "9") (name "/I2C1_SCL") (class "Default")
      (node (ref "I2C") (pin "3") (pinfunction "3_3") (pintype "passive"))
      (node (ref "J4") (pin "5") (pinfunction "5_5") (pintype "passive"))
    )
    (net (code "10") (name "/I2C1_SDA") (class "Default")
      (node (ref "I2C") (pin "2") (pinfunction "2_2") (pintype "passive"))
      (node (ref "J4") (pin "3") (pinfunction "3_3") (pintype "passive"))
    )
    (net (code "11") (name "/ID_SCL") (class "Default")
      (node (ref "J4") (pin "28") (pinfunction "28_28") (pintype "passive"))
      (node (ref "R16") (pin "P$2") (pinfunction "P$2_P$2") (pintype "passive"))
      (node (ref "U10") (pin "6") (pinfunction "SCL_6") (pintype "bidirectional"))
    )
    (net (code "12") (name "/ID_SDA") (class "Default")
      (node (ref "J4") (pin "27") (pinfunction "27_27") (pintype "passive"))
      (node (ref "R15") (pin "P$2") (pinfunction "P$2_P$2") (pintype "passive"))
      (node (ref "U10") (pin "5") (pinfunction "SDA_5") (pintype "bidirectional"))
    )
    (net (code "13") (name "/IFACEA_IRQ1") (class "Default")
      (node (ref "J4") (pin "37") (pinfunction "37_37") (pintype "passive"))
      (node (ref "U4") (pin "17") (pinfunction "PB0_17") (pintype "bidirectional"))
    )
    (net (code "14") (name "/IFACEB_IRQ1") (class "Default")
      (node (ref "J4") (pin "29") (pinfunction "29_29") (pintype "passive"))
      (node (ref "U11") (pin "17") (pinfunction "PB0_17") (pintype "bidirectional"))
    )
    (net (code "15") (name "/IMU2_CLKIN") (class "Default")
      (node (ref "U14") (pin "9") (pinfunction "INT2/FSYNC/CLKIN_9") (pintype "bidirectional"))
      (node (ref "U7") (pin "22") (pinfunction "PB10_22") (pintype "bidirectional"))
    )
    (net (code "16") (name "/IMU2_CS") (class "Default")
      (node (ref "U14") (pin "12") (pinfunction "AP_CS_12") (pintype "input"))
      (node (ref "U7") (pin "24") (pinfunction "PB11_24") (pintype "bidirectional"))
    )
    (net (code "17") (name "/IMU_ACC_INT") (class "Default")
      (node (ref "U7") (pin "32") (pinfunction "PA10_32") (pintype "bidirectional"))
      (node (ref "U8") (pin "16") (pinfunction "INT1_16") (pintype "bidirectional"))
    )
    (net (code "18") (name "/IMU_CS1") (class "Default")
      (node (ref "U7") (pin "31") (pinfunction "PA9_31") (pintype "bidirectional"))
      (node (ref "U8") (pin "14") (pinfunction "CSB1_14") (pintype "bidirectional"))
    )
    (net (code "19") (name "/IMU_CS2") (class "Default")
      (node (ref "U7") (pin "25") (pinfunction "PB12_25") (pintype "bidirectional"))
      (node (ref "U8") (pin "5") (pinfunction "CSB2_5") (pintype "bidirectional"))
    )
    (net (code "20") (name "/IMU_GYRO_INT") (class "Default")
      (node (ref "U14") (pin "4") (pinfunction "INT1/INT_4") (pintype "output"))
      (node (ref "U7") (pin "30") (pinfunction "PA8_30") (pintype "bidirectional"))
      (node (ref "U8") (pin "12") (pinfunction "INT3_12") (pintype "bidirectional"))
    )
    (net (code "21") (name "/IMU_MISO") (class "Default")
      (node (ref "U14") (pin "1") (pinfunction "AP_SDO/AP_AD0_1") (pintype "bidirectional"))
      (node (ref "U7") (pin "27") (pinfunction "PB14_27") (pintype "bidirectional"))
      (node (ref "U8") (pin "10") (pinfunction "SDO2_10") (pintype "bidirectional"))
      (node (ref "U8") (pin "15") (pinfunction "SDO1_15") (pintype "bidirectional"))
    )
    (net (code "22") (name "/IMU_MOSI") (class "Default")
      (node (ref "U14") (pin "14") (pinfunction "AP_SDA/AP_SDIO/AP_SDI_14") (pintype "bidirectional"))
      (node (ref "U7") (pin "28") (pinfunction "PB15_28") (pintype "bidirectional"))
      (node (ref "U8") (pin "9") (pinfunction "SDI_9") (pintype "bidirectional"))
    )
    (net (code "23") (name "/IMU_SCK") (class "Default")
      (node (ref "U14") (pin "13") (pinfunction "AP_SCL/AP_SCLK_13") (pintype "input"))
      (node (ref "U7") (pin "26") (pinfunction "PB13_26") (pintype "bidirectional"))
      (node (ref "U8") (pin "8") (pinfunction "SCK_8") (pintype "bidirectional"))
    )
    (net (code "24") (name "/PI32") (class "Default")
      (node (ref "J4") (pin "32") (pinfunction "32_32") (pintype "passive"))
      (node (ref "UT") (pin "1") (pinfunction "1_1") (pintype "passive"))
    )
    (net (code "25") (name "/PI33") (class "Default")
      (node (ref "J4") (pin "33") (pinfunction "33_33") (pintype "passive"))
      (node (ref "UT") (pin "2") (pinfunction "2_2") (pintype "passive"))
    )
    (net (code "26") (name "/PI_RX_3V") (class "Default")
      (node (ref "J4") (pin "10") (pinfunction "10_10") (pintype "passive"))
    )
    (net (code "27") (name "/PI_TX_3V") (class "Default")
      (node (ref "J4") (pin "8") (pinfunction "8_8") (pintype "passive"))
    )
    (net (code "28") (name "/REGOUT") (class "Default")
      (node (ref "C7") (pin "P$1") (pinfunction "P$1_P$1") (pintype "passive"))
      (node (ref "C8") (pin "P$1") (pinfunction "P$1_P$1") (pintype "passive"))
      (node (ref "L1") (pin "1") (pinfunction "1_1") (pintype "passive"))
      (node (ref "R2") (pin "P$1") (pinfunction "P$1_P$1") (pintype "passive"))
      (node (ref "REGOUT") (pin "P$1") (pinfunction "P$1_P$1") (pintype "bidirectional"))
      (node (ref "U2") (pin "5") (pinfunction "E2_5") (pintype "bidirectional"))
      (node (ref "U3") (pin "2") (pinfunction "S_2") (pintype "passive"))
    )
    (net (code "29") (name "/SPI0_CS0") (class "Default")
      (node (ref "J4") (pin "24") (pinfunction "24_24") (pintype "passive"))
      (node (ref "SPI0_CS0") (pin "P$1") (pinfunction "P$1_P$1") (pintype "bidirectional"))
      (node (ref "U7") (pin "12") (pinfunction "PA4_12") (pintype "bidirectional"))
    )
    (net (code "30") (name "/SPI0_CS1") (class "Default")
      (node (ref "J4") (pin "26") (pinfunction "26_26") (pintype "passive"))
    )
    (net (code "31") (name "/SPI0_MISO") (class "Default")
      (node (ref "R30") (pin "P$1") (pinfunction "P$1_P$1") (pintype "passive"))
      (node (ref "SPI0_MISO") (pin "P$1") (pinfunction "P$1_P$1") (pintype "bidirectional"))
      (node (ref "U7") (pin "14") (pinfunction "PA6_14") (pintype "bidirectional"))
    )
    (net (code "32") (name "/SPI0_MOSI") (class "Default")
      (node (ref "R29") (pin "P$1") (pinfunction "P$1_P$1") (pintype "passive"))
      (node (ref "SPI0_MOSI") (pin "P$1") (pinfunction "P$1_P$1") (pintype "bidirectional"))
      (node (ref "U7") (pin "15") (pinfunction "PA7_15") (pintype "bidirectional"))
    )
    (net (code "33") (name "/SPI0_SCLK") (class "Default")
      (node (ref "R31") (pin "P$1") (pinfunction "P$1_P$1") (pintype "passive"))
      (node (ref "SPI0_SCLK") (pin "P$1") (pinfunction "P$1_P$1") (pintype "bidirectional"))
      (node (ref "U7") (pin "13") (pinfunction "PA5_13") (pintype "bidirectional"))
    )
    (net (code "34") (name "/SPI1_CS0") (class "Default")
      (node (ref "J4") (pin "12") (pinfunction "12_12") (pintype "passive"))
      (node (ref "SPI1_CS0") (pin "P$1") (pinfunction "P$1_P$1") (pintype "bidirectional"))
      (node (ref "U4") (pin "12") (pinfunction "PA4_12") (pintype "bidirectional"))
    )
    (net (code "35") (name "/SPI1_CS1") (class "Default")
      (node (ref "J4") (pin "11") (pinfunction "11_11") (pintype "passive"))
      (node (ref "SPI1_CS1") (pin "P$1") (pinfunction "P$1_P$1") (pintype "bidirectional"))
      (node (ref "U11") (pin "12") (pinfunction "PA4_12") (pintype "bidirectional"))
    )
    (net (code "36") (name "/SPI1_CS2") (class "Default")
      (node (ref "J4") (pin "36") (pinfunction "36_36") (pintype "passive"))
    )
    (net (code "37") (name "/SPI1_MISO") (class "Default")
      (node (ref "R28") (pin "P$1") (pinfunction "P$1_P$1") (pintype "passive"))
      (node (ref "SPI1_MISO") (pin "P$1") (pinfunction "P$1_P$1") (pintype "bidirectional"))
      (node (ref "U11") (pin "14") (pinfunction "PA6_14") (pintype "bidirectional"))
      (node (ref "U4") (pin "14") (pinfunction "PA6_14") (pintype "bidirectional"))
    )
    (net (code "38") (name "/SPI1_MOSI") (class "Default")
      (node (ref "R26") (pin "P$2") (pinfunction "P$2_P$2") (pintype "passive"))
      (node (ref "SPI1_MOSI") (pin "P$1") (pinfunction "P$1_P$1") (pintype "bidirectional"))
      (node (ref "U11") (pin "15") (pinfunction "PA7_15") (pintype "bidirectional"))
      (node (ref "U4") (pin "15") (pinfunction "PA7_15") (pintype "bidirectional"))
    )
    (net (code "39") (name "/SPI1_SCLK") (class "Default")
      (node (ref "R27") (pin "P$2") (pinfunction "P$2_P$2") (pintype "passive"))
      (node (ref "SPI1_SCLK") (pin "P$1") (pinfunction "P$1_P$1") (pintype "bidirectional"))
      (node (ref "U11") (pin "13") (pinfunction "PA5_13") (pintype "bidirectional"))
      (node (ref "U4") (pin "13") (pinfunction "PA5_13") (pintype "bidirectional"))
    )
    (net (code "40") (name "/V+") (class "Default")
      (node (ref "F1") (pin "1") (pinfunction "1_1") (pintype "passive"))
      (node (ref "J1") (pin "2") (pinfunction "2_2") (pintype "passive"))
      (node (ref "J2") (pin "2") (pinfunction "2_2") (pintype "passive"))
      (node (ref "R21") (pin "P$1") (pinfunction "P$1_P$1") (pintype "passive"))
      (node (ref "V+") (pin "P$1") (pinfunction "P$1_P$1") (pintype "bidirectional"))
    )
    (net (code "41") (name "/V+FUSED") (class "Default")
      (node (ref "C1") (pin "P$1") (pinfunction "P$1_P$1") (pintype "passive"))
      (node (ref "C2") (pin "P$1") (pinfunction "P$1_P$1") (pintype "passive"))
      (node (ref "C3") (pin "P$1") (pinfunction "P$1_P$1") (pintype "passive"))
      (node (ref "D12") (pin "C") (pinfunction "C_C") (pintype "passive"))
      (node (ref "F1") (pin "2") (pinfunction "2_2") (pintype "passive"))
      (node (ref "U1") (pin "1") (pinfunction "VIN_2_1") (pintype "passive"))
      (node (ref "U1") (pin "2") (pinfunction "VIN_3_2") (pintype "passive"))
      (node (ref "U1") (pin "3") (pinfunction "VIN_3") (pintype "passive"))
      (node (ref "U1") (pin "4") (pinfunction "EN/UVLO_4") (pintype "passive"))
    )
    (net (code "42") (name "/V+SENSE") (class "Default")
      (node (ref "R1") (pin "P$1") (pinfunction "P$1_P$1") (pintype "passive"))
      (node (ref "R21") (pin "P$2") (pinfunction "P$2_P$2") (pintype "passive"))
      (node (ref "U7") (pin "16") (pinfunction "PC4_16") (pintype "bidirectional"))
    )
    (net (code "43") (name "GND") (class "Default")
      (node (ref "C1") (pin "P$2") (pinfunction "P$2_P$2") (pintype "passive"))
      (node (ref "C10") (pin "P$2") (pinfunction "P$2_P$2") (pintype "passive"))
      (node (ref "C11") (pin "P$2") (pinfunction "P$2_P$2") (pintype "passive"))
      (node (ref "C12") (pin "P$2") (pinfunction "P$2_P$2") (pintype "passive"))
      (node (ref "C13") (pin "P$2") (pinfunction "P$2_P$2") (pintype "passive"))
      (node (ref "C14") (pin "P$2") (pinfunction "P$2_P$2") (pintype "passive"))
      (node (ref "C15") (pin "P$2") (pinfunction "P$2_P$2") (pintype "passive"))
      (node (ref "C16") (pin "P$2") (pinfunction "P$2_P$2") (pintype "passive"))
      (node (ref "C17") (pin "P$2") (pinfunction "P$2_P$2") (pintype "passive"))
      (node (ref "C18") (pin "P$2") (pinfunction "P$2_P$2") (pintype "passive"))
      (node (ref "C19") (pin "P$2") (pinfunction "P$2_P$2") (pintype "passive"))
      (node (ref "C2") (pin "P$2") (pinfunction "P$2_P$2") (pintype "passive"))
      (node (ref "C20") (pin "P$2") (pinfunction "P$2_P$2") (pintype "passive"))
      (node (ref "C21") (pin "P$2") (pinfunction "P$2_P$2") (pintype "passive"))
      (node (ref "C22") (pin "P$2") (pinfunction "P$2_P$2") (pintype "passive"))
      (node (ref "C23") (pin "P$2") (pinfunction "P$2_P$2") (pintype "passive"))
      (node (ref "C24") (pin "P$2") (pinfunction "P$2_P$2") (pintype "passive"))
      (node (ref "C25") (pin "P$2") (pinfunction "P$2_P$2") (pintype "passive"))
      (node (ref "C26") (pin "P$2") (pinfunction "P$2_P$2") (pintype "passive"))
      (node (ref "C27") (pin "P$2") (pinfunction "P$2_P$2") (pintype "passive"))
      (node (ref "C28") (pin "P$2") (pinfunction "P$2_P$2") (pintype "passive"))
      (node (ref "C29") (pin "P$2") (pinfunction "P$2_P$2") (pintype "passive"))
      (node (ref "C3") (pin "P$2") (pinfunction "P$2_P$2") (pintype "passive"))
      (node (ref "C30") (pin "P$2") (pinfunction "P$2_P$2") (pintype "passive"))
      (node (ref "C31") (pin "P$2") (pinfunction "P$2_P$2") (pintype "passive"))
      (node (ref "C32") (pin "P$2") (pinfunction "P$2_P$2") (pintype "passive"))
      (node (ref "C33") (pin "P$2") (pinfunction "P$2_P$2") (pintype "passive"))
      (node (ref "C34") (pin "P$2") (pinfunction "P$2_P$2") (pintype "passive"))
      (node (ref "C35") (pin "P$2") (pinfunction "P$2_P$2") (pintype "passive"))
      (node (ref "C36") (pin "P$2") (pinfunction "P$2_P$2") (pintype "passive"))
      (node (ref "C37") (pin "P$2") (pinfunction "P$2_P$2") (pintype "passive"))
      (node (ref "C38") (pin "P$2") (pinfunction "P$2_P$2") (pintype "passive"))
      (node (ref "C39") (pin "P$2") (pinfunction "P$2_P$2") (pintype "passive"))
      (node (ref "C4") (pin "P$2") (pinfunction "P$2_P$2") (pintype "passive"))
      (node (ref "C40") (pin "P$2") (pinfunction "P$2_P$2") (pintype "passive"))
      (node (ref "C41") (pin "P$2") (pinfunction "P$2_P$2") (pintype "passive"))
      (node (ref "C42") (pin "P$2") (pinfunction "P$2_P$2") (pintype "passive"))
      (node (ref "C43") (pin "P$2") (pinfunction "P$2_P$2") (pintype "passive"))
      (node (ref "C44") (pin "P$2") (pinfunction "P$2_P$2") (pintype "passive"))
      (node (ref "C45") (pin "P$2") (pinfunction "P$2_P$2") (pintype "passive"))
      (node (ref "C46") (pin "P$2") (pinfunction "P$2_P$2") (pintype "passive"))
      (node (ref "C6") (pin "P$2") (pinfunction "P$2_P$2") (pintype "passive"))
      (node (ref "C7") (pin "P$2") (pinfunction "P$2_P$2") (pintype "passive"))
      (node (ref "C8") (pin "P$2") (pinfunction "P$2_P$2") (pintype "passive"))
      (node (ref "C9") (pin "P$2") (pinfunction "P$2_P$2") (pintype "passive"))
      (node (ref "D1") (pin "CATHODE") (pinfunction "CATHODE_CATHODE") (pintype "power_in"))
      (node (ref "D12") (pin "A") (pinfunction "A_A") (pintype "passive"))
      (node (ref "GND") (pin "P$1") (pinfunction "P$1_P$1") (pintype "bidirectional"))
      (node (ref "I2C") (pin "4") (pinfunction "4_4") (pintype "passive"))
      (node (ref "J1") (pin "1") (pinfunction "1_1") (pintype "passive"))
      (node (ref "J2") (pin "1") (pinfunction "1_1") (pintype "passive"))
      (node (ref "J4") (pin "14") (pinfunction "14_14") (pintype "passive"))
      (node (ref "J4") (pin "20") (pinfunction "20_20") (pintype "passive"))
      (node (ref "J4") (pin "25") (pinfunction "25_25") (pintype "passive"))
      (node (ref "J4") (pin "30") (pinfunction "30_30") (pintype "passive"))
      (node (ref "J4") (pin "34") (pinfunction "34_34") (pintype "passive"))
      (node (ref "J4") (pin "39") (pinfunction "39_39") (pintype "passive"))
      (node (ref "J4") (pin "6") (pinfunction "6_6") (pintype "passive"))
      (node (ref "J4") (pin "9") (pinfunction "9_9") (pintype "passive"))
      (node (ref "JC1") (pin "3") (pinfunction "3_3") (pintype "passive"))
      (node (ref "JC2") (pin "3") (pinfunction "3_3") (pintype "passive"))
      (node (ref "JC3") (pin "3") (pinfunction "3_3") (pintype "passive"))
      (node (ref "JC4") (pin "3") (pinfunction "3_3") (pintype "passive"))
      (node (ref "JC5") (pin "3") (pinfunction "3_3") (pintype "passive"))
      (node (ref "JD1") (pin "4") (pinfunction "4_4") (pintype "passive"))
      (node (ref "JD2") (pin "4") (pinfunction "4_4") (pintype "passive"))
      (node (ref "JD3") (pin "4") (pinfunction "4_4") (pintype "passive"))
      (node (ref "JP6") (pin "3") (pinfunction "3_3") (pintype "passive"))
      (node (ref "JP7") (pin "1") (pinfunction "1_1") (pintype "passive"))
      (node (ref "R1") (pin "P$2") (pinfunction "P$2_P$2") (pintype "passive"))
      (node (ref "R24") (pin "P$2") (pinfunction "P$2_P$2") (pintype "passive"))
      (node (ref "R3") (pin "P$2") (pinfunction "P$2_P$2") (pintype "passive"))
      (node (ref "R5") (pin "P$2") (pinfunction "P$2_P$2") (pintype "passive"))
      (node (ref "R6") (pin "P$2") (pinfunction "P$2_P$2") (pintype "passive"))
      (node (ref "U1") (pin "13") (pinfunction "SGND_13") (pintype "passive"))
      (node (ref "U1") (pin "14") (pinfunction "PGND_2_14") (pintype "passive"))
      (node (ref "U1") (pin "15") (pinfunction "PGND_3_15") (pintype "passive"))
      (node (ref "U1") (pin "16") (pinfunction "PGND_16") (pintype "passive"))
      (node (ref "U1") (pin "21") (pinfunction "EPAD_21") (pintype "passive"))
      (node (ref "U1") (pin "22") (pinfunction "EPAD_22") (pintype "passive"))
      (node (ref "U1") (pin "23") (pinfunction "EPAD_23") (pintype "passive"))
      (node (ref "U1") (pin "24") (pinfunction "EPAD_24") (pintype "passive"))
      (node (ref "U1") (pin "25") (pinfunction "EPAD_25") (pintype "passive"))
      (node (ref "U1") (pin "26") (pinfunction "EPAD_26") (pintype "passive"))
      (node (ref "U1") (pin "27") (pinfunction "EPAD_27") (pintype "passive"))
      (node (ref "U1") (pin "28") (pinfunction "EPAD_28") (pintype "passive"))
      (node (ref "U1") (pin "29") (pinfunction "EPAD_29") (pintype "passive"))
      (node (ref "U1") (pin "30") (pinfunction "EPAD_30") (pintype "passive"))
      (node (ref "U10") (pin "1") (pinfunction "A0_1") (pintype "bidirectional"))
      (node (ref "U10") (pin "2") (pinfunction "A1_2") (pintype "bidirectional"))
      (node (ref "U10") (pin "3") (pinfunction "A2_3") (pintype "bidirectional"))
      (node (ref "U10") (pin "4") (pinfunction "VSS_4") (pintype "bidirectional"))
      (node (ref "U11") (pin "3") (pinfunction "PC14-OSC32_IN_3") (pintype "bidirectional"))
      (node (ref "U11") (pin "49") (pinfunction "THERMALPAD_49") (pintype "bidirectional"))
      (node (ref "U12") (pin "2") (pinfunction "GND_2") (pintype "power_in"))
      (node (ref "U12") (pin "8") (pinfunction "RS_8") (pintype "input"))
      (node (ref "U13") (pin "2") (pinfunction "GND_2") (pintype "power_in"))
      (node (ref "U13") (pin "8") (pinfunction "RS_8") (pintype "input"))
      (node (ref "U14") (pin "6") (pinfunction "GND_6") (pintype "power_in"))
      (node (ref "U4") (pin "3") (pinfunction "PC14-OSC32_IN_3") (pintype "bidirectional"))
      (node (ref "U4") (pin "4") (pinfunction "PC15-OSC32_OUT_4") (pintype "bidirectional"))
      (node (ref "U4") (pin "49") (pinfunction "THERMALPAD_49") (pintype "bidirectional"))
      (node (ref "U5") (pin "2") (pinfunction "GND_2") (pintype "power_in"))
      (node (ref "U5") (pin "8") (pinfunction "RS_8") (pintype "input"))
      (node (ref "U6") (pin "2") (pinfunction "GND_2") (pintype "power_in"))
      (node (ref "U6") (pin "8") (pinfunction "RS_8") (pintype "input"))
      (node (ref "U7") (pin "4") (pinfunction "PC15-OSC32_OUT_4") (pintype "bidirectional"))
      (node (ref "U7") (pin "49") (pinfunction "THERMALPAD_49") (pintype "bidirectional"))
      (node (ref "U8") (pin "4") (pinfunction "GND_4") (pintype "bidirectional"))
      (node (ref "U8") (pin "6") (pinfunction "GNDIO_6") (pintype "bidirectional"))
      (node (ref "U8") (pin "7") (pinfunction "PS_7") (pintype "bidirectional"))
      (node (ref "U9") (pin "2") (pinfunction "GND_2") (pintype "power_in"))
      (node (ref "U9") (pin "8") (pinfunction "RS_8") (pintype "input"))
      (node (ref "UT") (pin "3") (pinfunction "3_3") (pintype "passive"))
    )
    (net (code "44") (name "Net-(D1-PadANODE)") (class "Default")
      (node (ref "D1") (pin "ANODE") (pinfunction "ANODE_ANODE") (pintype "power_in"))
      (node (ref "R4") (pin "P$2") (pinfunction "P$2_P$2") (pintype "passive"))
    )
    (net (code "45") (name "Net-(D2-PadANODE)") (class "Default")
      (node (ref "D2") (pin "ANODE") (pinfunction "ANODE_ANODE") (pintype "power_in"))
      (node (ref "R7") (pin "P$2") (pinfunction "P$2_P$2") (pintype "passive"))
    )
    (net (code "46") (name "Net-(D3-PadANODE)") (class "Default")
      (node (ref "D3") (pin "ANODE") (pinfunction "ANODE_ANODE") (pintype "power_in"))
      (node (ref "R8") (pin "P$2") (pinfunction "P$2_P$2") (pintype "passive"))
    )
    (net (code "47") (name "Net-(D4-PadANODE)") (class "Default")
      (node (ref "D4") (pin "ANODE") (pinfunction "ANODE_ANODE") (pintype "power_in"))
      (node (ref "R11") (pin "P$2") (pinfunction "P$2_P$2") (pintype "passive"))
    )
    (net (code "48") (name "Net-(D5-PadANODE)") (class "Default")
      (node (ref "D5") (pin "ANODE") (pinfunction "ANODE_ANODE") (pintype "power_in"))
      (node (ref "R12") (pin "P$2") (pinfunction "P$2_P$2") (pintype "passive"))
    )
    (net (code "49") (name "Net-(D6-PadANODE)") (class "Default")
      (node (ref "D6") (pin "ANODE") (pinfunction "ANODE_ANODE") (pintype "power_in"))
      (node (ref "R17") (pin "P$2") (pinfunction "P$2_P$2") (pintype "passive"))
    )
    (net (code "50") (name "Net-(D7-PadANODE)") (class "Default")
      (node (ref "D7") (pin "ANODE") (pinfunction "ANODE_ANODE") (pintype "power_in"))
      (node (ref "R18") (pin "P$2") (pinfunction "P$2_P$2") (pintype "passive"))
    )
    (net (code "51") (name "Net-(J4-Pad19)") (class "Default")
      (node (ref "J4") (pin "19") (pinfunction "19_19") (pintype "passive"))
      (node (ref "R29") (pin "P$2") (pinfunction "P$2_P$2") (pintype "passive"))
    )
    (net (code "52") (name "Net-(J4-Pad21)") (class "Default")
      (node (ref "J4") (pin "21") (pinfunction "21_21") (pintype "passive"))
      (node (ref "R30") (pin "P$2") (pinfunction "P$2_P$2") (pintype "passive"))
    )
    (net (code "53") (name "Net-(J4-Pad23)") (class "Default")
      (node (ref "J4") (pin "23") (pinfunction "23_23") (pintype "passive"))
      (node (ref "R31") (pin "P$2") (pinfunction "P$2_P$2") (pintype "passive"))
    )
    (net (code "54") (name "Net-(J4-Pad35)") (class "Default")
      (node (ref "J4") (pin "35") (pinfunction "35_35") (pintype "passive"))
      (node (ref "R28") (pin "P$2") (pinfunction "P$2_P$2") (pintype "passive"))
    )
    (net (code "55") (name "Net-(J4-Pad38)") (class "Default")
      (node (ref "J4") (pin "38") (pinfunction "38_38") (pintype "passive"))
      (node (ref "R26") (pin "P$1") (pinfunction "P$1_P$1") (pintype "passive"))
    )
    (net (code "56") (name "Net-(J4-Pad40)") (class "Default")
      (node (ref "J4") (pin "40") (pinfunction "40_40") (pintype "passive"))
      (node (ref "R27") (pin "P$1") (pinfunction "P$1_P$1") (pintype "passive"))
    )
    (net (code "57") (name "Net-(U1-BST)") (class "Default")
      (node (ref "C5") (pin "P$1") (pinfunction "P$1_P$1") (pintype "passive"))
      (node (ref "U1") (pin "20") (pinfunction "BST_20") (pintype "passive"))
    )
    (net (code "58") (name "Net-(U1-FB)") (class "Default")
      (node (ref "R2") (pin "P$2") (pinfunction "P$2_P$2") (pintype "passive"))
      (node (ref "R3") (pin "P$1") (pinfunction "P$1_P$1") (pintype "passive"))
      (node (ref "U1") (pin "9") (pinfunction "FB_9") (pintype "passive"))
    )
    (net (code "59") (name "Net-(U1-SS)") (class "Default")
      (node (ref "C4") (pin "P$1") (pinfunction "P$1_P$1") (pintype "passive"))
      (node (ref "U1") (pin "7") (pinfunction "SS_7") (pintype "passive"))
    )
    (net (code "60") (name "Net-(U1-VCC)") (class "Default")
      (node (ref "C6") (pin "P$1") (pinfunction "P$1_P$1") (pintype "passive"))
      (node (ref "U1") (pin "12") (pinfunction "VCC_12") (pintype "power_in"))
    )
    (net (code "61") (name "Net-(U2-B1)") (class "Default")
      (node (ref "R5") (pin "P$1") (pinfunction "P$1_P$1") (pintype "passive"))
      (node (ref "U2") (pin "2") (pinfunction "B1_2") (pintype "bidirectional"))
      (node (ref "U2") (pin "3") (pinfunction "B2_3") (pintype "bidirectional"))
      (node (ref "U2") (pin "4") (pinfunction "C2_4") (pintype "bidirectional"))
    )
    (net (code "62") (name "Net-(U2-C1)") (class "Default")
      (node (ref "R6") (pin "P$1") (pinfunction "P$1_P$1") (pintype "passive"))
      (node (ref "U2") (pin "1") (pinfunction "C1_1") (pintype "bidirectional"))
      (node (ref "U3") (pin "1") (pinfunction "G_1") (pintype "passive"))
    )
    (net (code "63") (name "Net-(U4-PA11)") (class "Default")
      (node (ref "U4") (pin "33") (pinfunction "PA11_33") (pintype "bidirectional"))
      (node (ref "U5") (pin "4") (pinfunction "RXD_4") (pintype "output"))
    )
    (net (code "64") (name "Net-(U4-PA12)") (class "Default")
      (node (ref "U4") (pin "34") (pinfunction "PA12_34") (pintype "bidirectional"))
      (node (ref "U5") (pin "1") (pinfunction "TXD_1") (pintype "input"))
    )
    (net (code "65") (name "Net-(U4-PA13)") (class "Default")
      (node (ref "JD1") (pin "3") (pinfunction "3_3") (pintype "passive"))
      (node (ref "U4") (pin "36") (pinfunction "PA13_36") (pintype "bidirectional"))
    )
    (net (code "66") (name "Net-(U4-PA14)") (class "Default")
      (node (ref "JD1") (pin "5") (pinfunction "5_5") (pintype "passive"))
      (node (ref "U4") (pin "37") (pinfunction "PA14_37") (pintype "bidirectional"))
    )
    (net (code "67") (name "Net-(U4-PB3)") (class "Default")
      (node (ref "U4") (pin "41") (pinfunction "PB3_41") (pintype "bidirectional"))
      (node (ref "U6") (pin "4") (pinfunction "RXD_4") (pintype "output"))
    )
    (net (code "68") (name "Net-(U4-PB4)") (class "Default")
      (node (ref "U4") (pin "42") (pinfunction "PB4_42") (pintype "bidirectional"))
      (node (ref "U6") (pin "1") (pinfunction "TXD_1") (pintype "input"))
    )
    (net (code "69") (name "Net-(U4-PF0-OSC_IN)") (class "Default")
      (node (ref "D3") (pin "CATHODE") (pinfunction "CATHODE_CATHODE") (pintype "power_in"))
      (node (ref "U4") (pin "5") (pinfunction "PF0-OSC_IN_5") (pintype "bidirectional"))
    )
    (net (code "70") (name "Net-(U4-PF1-OSC_OUT)") (class "Default")
      (node (ref "D2") (pin "CATHODE") (pinfunction "CATHODE_CATHODE") (pintype "power_in"))
      (node (ref "U4") (pin "6") (pinfunction "PF1-OSC_OUT_6") (pintype "bidirectional"))
    )
    (net (code "71") (name "Net-(U4-PG10-NRST)") (class "Default")
      (node (ref "C9") (pin "P$1") (pinfunction "P$1_P$1") (pintype "passive"))
      (node (ref "JD1") (pin "2") (pinfunction "2_2") (pintype "passive"))
      (node (ref "U4") (pin "7") (pinfunction "PG10-NRST_7") (pintype "bidirectional"))
    )
    (net (code "72") (name "Net-(U5-CANH)") (class "Default")
      (node (ref "JC2") (pin "1") (pinfunction "1_1") (pintype "passive"))
      (node (ref "R10") (pin "P$1") (pinfunction "P$1_P$1") (pintype "passive"))
      (node (ref "U5") (pin "7") (pinfunction "CANH_7") (pintype "bidirectional"))
    )
    (net (code "73") (name "Net-(U5-CANL)") (class "Default")
      (node (ref "JC2") (pin "2") (pinfunction "2_2") (pintype "passive"))
      (node (ref "R10") (pin "P$2") (pinfunction "P$2_P$2") (pintype "passive"))
      (node (ref "U5") (pin "6") (pinfunction "CANL_6") (pintype "bidirectional"))
    )
    (net (code "74") (name "Net-(U6-CANH)") (class "Default")
      (node (ref "JC1") (pin "1") (pinfunction "1_1") (pintype "passive"))
      (node (ref "R9") (pin "P$1") (pinfunction "P$1_P$1") (pintype "passive"))
      (node (ref "U6") (pin "7") (pinfunction "CANH_7") (pintype "bidirectional"))
    )
    (net (code "75") (name "Net-(U6-CANL)") (class "Default")
      (node (ref "JC1") (pin "2") (pinfunction "2_2") (pintype "passive"))
      (node (ref "R9") (pin "P$2") (pinfunction "P$2_P$2") (pintype "passive"))
      (node (ref "U6") (pin "6") (pinfunction "CANL_6") (pintype "bidirectional"))
    )
    (net (code "76") (name "Net-(U7-PA11)") (class "Default")
      (node (ref "U7") (pin "33") (pinfunction "PA11_33") (pintype "bidirectional"))
      (node (ref "U9") (pin "4") (pinfunction "RXD_4") (pintype "output"))
    )
    (net (code "77") (name "Net-(U7-PA12)") (class "Default")
      (node (ref "U7") (pin "34") (pinfunction "PA12_34") (pintype "bidirectional"))
      (node (ref "U9") (pin "1") (pinfunction "TXD_1") (pintype "input"))
    )
    (net (code "78") (name "Net-(U7-PA13)") (class "Default")
      (node (ref "JD3") (pin "3") (pinfunction "3_3") (pintype "passive"))
      (node (ref "U7") (pin "36") (pinfunction "PA13_36") (pintype "bidirectional"))
    )
    (net (code "79") (name "Net-(U7-PA14)") (class "Default")
      (node (ref "JD3") (pin "5") (pinfunction "5_5") (pintype "passive"))
      (node (ref "U7") (pin "37") (pinfunction "PA14_37") (pintype "bidirectional"))
    )
    (net (code "80") (name "Net-(U7-PF0-OSC_IN)") (class "Default")
      (node (ref "D5") (pin "CATHODE") (pinfunction "CATHODE_CATHODE") (pintype "power_in"))
      (node (ref "U7") (pin "5") (pinfunction "PF0-OSC_IN_5") (pintype "bidirectional"))
    )
    (net (code "81") (name "Net-(U7-PF1-OSC_OUT)") (class "Default")
      (node (ref "D4") (pin "CATHODE") (pinfunction "CATHODE_CATHODE") (pintype "power_in"))
      (node (ref "U7") (pin "6") (pinfunction "PF1-OSC_OUT_6") (pintype "bidirectional"))
    )
    (net (code "82") (name "Net-(U7-PG10-NRST)") (class "Default")
      (node (ref "C18") (pin "P$1") (pinfunction "P$1_P$1") (pintype "passive"))
      (node (ref "JD3") (pin "2") (pinfunction "2_2") (pintype "passive"))
      (node (ref "U7") (pin "7") (pinfunction "PG10-NRST_7") (pintype "bidirectional"))
    )
    (net (code "83") (name "Net-(U9-CANH)") (class "Default")
      (node (ref "JC5") (pin "1") (pinfunction "1_1") (pintype "passive"))
      (node (ref "R13") (pin "P$1") (pinfunction "P$1_P$1") (pintype "passive"))
      (node (ref "U9") (pin "7") (pinfunction "CANH_7") (pintype "bidirectional"))
    )
    (net (code "84") (name "Net-(U9-CANL)") (class "Default")
      (node (ref "JC5") (pin "2") (pinfunction "2_2") (pintype "passive"))
      (node (ref "R13") (pin "P$2") (pinfunction "P$2_P$2") (pintype "passive"))
      (node (ref "U9") (pin "6") (pinfunction "CANL_6") (pintype "bidirectional"))
    )
    (net (code "85") (name "Net-(U10-WP)") (class "Default")
      (node (ref "JP8") (pin "1") (pinfunction "1_1") (pintype "passive"))
      (node (ref "R14") (pin "P$2") (pinfunction "P$2_P$2") (pintype "passive"))
      (node (ref "U10") (pin "7") (pinfunction "WP_7") (pintype "bidirectional"))
    )
    (net (code "86") (name "Net-(U11-PA11)") (class "Default")
      (node (ref "U11") (pin "33") (pinfunction "PA11_33") (pintype "bidirectional"))
      (node (ref "U13") (pin "4") (pinfunction "RXD_4") (pintype "output"))
    )
    (net (code "87") (name "Net-(U11-PA12)") (class "Default")
      (node (ref "U11") (pin "34") (pinfunction "PA12_34") (pintype "bidirectional"))
      (node (ref "U13") (pin "1") (pinfunction "TXD_1") (pintype "input"))
    )
    (net (code "88") (name "Net-(U11-PA13)") (class "Default")
      (node (ref "JD2") (pin "3") (pinfunction "3_3") (pintype "passive"))
      (node (ref "U11") (pin "36") (pinfunction "PA13_36") (pintype "bidirectional"))
    )
    (net (code "89") (name "Net-(U11-PA14)") (class "Default")
      (node (ref "JD2") (pin "5") (pinfunction "5_5") (pintype "passive"))
      (node (ref "U11") (pin "37") (pinfunction "PA14_37") (pintype "bidirectional"))
    )
    (net (code "90") (name "Net-(U11-PB3)") (class "Default")
      (node (ref "U11") (pin "41") (pinfunction "PB3_41") (pintype "bidirectional"))
      (node (ref "U12") (pin "4") (pinfunction "RXD_4") (pintype "output"))
    )
    (net (code "91") (name "Net-(U11-PB4)") (class "Default")
      (node (ref "U11") (pin "42") (pinfunction "PB4_42") (pintype "bidirectional"))
      (node (ref "U12") (pin "1") (pinfunction "TXD_1") (pintype "input"))
    )
    (net (code "92") (name "Net-(U11-PF0-OSC_IN)") (class "Default")
      (node (ref "D7") (pin "CATHODE") (pinfunction "CATHODE_CATHODE") (pintype "power_in"))
      (node (ref "U11") (pin "5") (pinfunction "PF0-OSC_IN_5") (pintype "bidirectional"))
    )
    (net (code "93") (name "Net-(U11-PF1-OSC_OUT)") (class "Default")
      (node (ref "D6") (pin "CATHODE") (pinfunction "CATHODE_CATHODE") (pintype "power_in"))
      (node (ref "U11") (pin "6") (pinfunction "PF1-OSC_OUT_6") (pintype "bidirectional"))
    )
    (net (code "94") (name "Net-(U11-PG10-NRST)") (class "Default")
      (node (ref "C32") (pin "P$1") (pinfunction "P$1_P$1") (pintype "passive"))
      (node (ref "JD2") (pin "2") (pinfunction "2_2") (pintype "passive"))
      (node (ref "U11") (pin "7") (pinfunction "PG10-NRST_7") (pintype "bidirectional"))
    )
    (net (code "95") (name "Net-(U12-CANH)") (class "Default")
      (node (ref "JC3") (pin "1") (pinfunction "1_1") (pintype "passive"))
      (node (ref "R19") (pin "P$1") (pinfunction "P$1_P$1") (pintype "passive"))
      (node (ref "U12") (pin "7") (pinfunction "CANH_7") (pintype "bidirectional"))
    )
    (net (code "96") (name "Net-(U12-CANL)") (class "Default")
      (node (ref "JC3") (pin "2") (pinfunction "2_2") (pintype "passive"))
      (node (ref "R19") (pin "P$2") (pinfunction "P$2_P$2") (pintype "passive"))
      (node (ref "U12") (pin "6") (pinfunction "CANL_6") (pintype "bidirectional"))
    )
    (net (code "97") (name "Net-(U13-CANH)") (class "Default")
      (node (ref "JC4") (pin "1") (pinfunction "1_1") (pintype "passive"))
      (node (ref "R20") (pin "P$1") (pinfunction "P$1_P$1") (pintype "passive"))
      (node (ref "U13") (pin "7") (pinfunction "CANH_7") (pintype "bidirectional"))
    )
    (net (code "98") (name "Net-(U13-CANL)") (class "Default")
      (node (ref "JC4") (pin "2") (pinfunction "2_2") (pintype "passive"))
      (node (ref "R20") (pin "P$2") (pinfunction "P$2_P$2") (pintype "passive"))
      (node (ref "U13") (pin "6") (pinfunction "CANL_6") (pintype "bidirectional"))
    )
    (net (code "99") (name "unconnected-(J4-Pad7)") (class "Default")
      (node (ref "J4") (pin "7") (pinfunction "7_7") (pintype "passive"))
    )
    (net (code "100") (name "unconnected-(J4-Pad13)") (class "Default")
      (node (ref "J4") (pin "13") (pinfunction "13_13") (pintype "passive"))
    )
    (net (code "101") (name "unconnected-(J4-Pad22)") (class "Default")
      (node (ref "J4") (pin "22") (pinfunction "22_22") (pintype "passive"))
    )
    (net (code "102") (name "unconnected-(J4-Pad31)") (class "Default")
      (node (ref "J4") (pin "31") (pinfunction "31_31") (pintype "passive"))
    )
    (net (code "103") (name "unconnected-(JD1-Pad1)") (class "Default")
      (node (ref "JD1") (pin "1") (pinfunction "1_1") (pintype "passive"))
    )
    (net (code "104") (name "unconnected-(JD2-Pad1)") (class "Default")
      (node (ref "JD2") (pin "1") (pinfunction "1_1") (pintype "passive"))
    )
    (net (code "105") (name "unconnected-(JD3-Pad1)") (class "Default")
      (node (ref "JD3") (pin "1") (pinfunction "1_1") (pintype "passive"))
    )
    (net (code "106") (name "unconnected-(U1-CF-Pad8)") (class "Default")
      (node (ref "U1") (pin "8") (pinfunction "CF_8") (pintype "passive"))
    )
    (net (code "107") (name "unconnected-(U1-MODE-Pad11)") (class "Default")
      (node (ref "U1") (pin "11") (pinfunction "MODE_11") (pintype "passive"))
    )
    (net (code "108") (name "unconnected-(U1-RT-Pad10)") (class "Default")
      (node (ref "U1") (pin "10") (pinfunction "RT_10") (pintype "passive"))
    )
    (net (code "109") (name "unconnected-(U1-SYNC-Pad6)") (class "Default")
      (node (ref "U1") (pin "6") (pinfunction "SYNC_6") (pintype "passive"))
    )
    (net (code "110") (name "unconnected-(U1-~{RESET}-Pad5)") (class "Default")
      (node (ref "U1") (pin "5") (pinfunction "~{RESET}_5") (pintype "passive"))
    )
    (net (code "111") (name "unconnected-(U4-PA0-Pad8)") (class "Default")
      (node (ref "U4") (pin "8") (pinfunction "PA0_8") (pintype "bidirectional"))
    )
    (net (code "112") (name "unconnected-(U4-PA1-Pad9)") (class "Default")
      (node (ref "U4") (pin "9") (pinfunction "PA1_9") (pintype "bidirectional"))
    )
    (net (code "113") (name "unconnected-(U4-PA2-Pad10)") (class "Default")
      (node (ref "U4") (pin "10") (pinfunction "PA2_10") (pintype "bidirectional"))
    )
    (net (code "114") (name "unconnected-(U4-PA3-Pad11)") (class "Default")
      (node (ref "U4") (pin "11") (pinfunction "PA3_11") (pintype "bidirectional"))
    )
    (net (code "115") (name "unconnected-(U4-PA8-Pad30)") (class "Default")
      (node (ref "U4") (pin "30") (pinfunction "PA8_30") (pintype "bidirectional"))
    )
    (net (code "116") (name "unconnected-(U4-PA9-Pad31)") (class "Default")
      (node (ref "U4") (pin "31") (pinfunction "PA9_31") (pintype "bidirectional"))
    )
    (net (code "117") (name "unconnected-(U4-PA10-Pad32)") (class "Default")
      (node (ref "U4") (pin "32") (pinfunction "PA10_32") (pintype "bidirectional"))
    )
    (net (code "118") (name "unconnected-(U4-PA15-Pad38)") (class "Default")
      (node (ref "U4") (pin "38") (pinfunction "PA15_38") (pintype "bidirectional"))
    )
    (net (code "119") (name "unconnected-(U4-PB1-Pad18)") (class "Default")
      (node (ref "U4") (pin "18") (pinfunction "PB1_18") (pintype "bidirectional"))
    )
    (net (code "120") (name "unconnected-(U4-PB2-Pad19)") (class "Default")
      (node (ref "U4") (pin "19") (pinfunction "PB2_19") (pintype "bidirectional"))
    )
    (net (code "121") (name "unconnected-(U4-PB5-Pad43)") (class "Default")
      (node (ref "U4") (pin "43") (pinfunction "PB5_43") (pintype "bidirectional"))
    )
    (net (code "122") (name "unconnected-(U4-PB6-Pad44)") (class "Default")
      (node (ref "U4") (pin "44") (pinfunction "PB6_44") (pintype "bidirectional"))
    )
    (net (code "123") (name "unconnected-(U4-PB7-Pad45)") (class "Default")
      (node (ref "U4") (pin "45") (pinfunction "PB7_45") (pintype "bidirectional"))
    )
    (net (code "124") (name "unconnected-(U4-PB8-BOOT0-Pad46)") (class "Default")
      (node (ref "U4") (pin "46") (pinfunction "PB8-BOOT0_46") (pintype "bidirectional"))
    )
    (net (code "125") (name "unconnected-(U4-PB9-Pad47)") (class "Default")
      (node (ref "U4") (pin "47") (pinfunction "PB9_47") (pintype "bidirectional"))
    )
    (net (code "126") (name "unconnected-(U4-PB10-Pad22)") (class "Default")
      (node (ref "U4") (pin "22") (pinfunction "PB10_22") (pintype "bidirectional"))
    )
    (net (code "127") (name "unconnected-(U4-PB11-Pad24)") (class "Default")
      (node (ref "U4") (pin "24") (pinfunction "PB11_24") (pintype "bidirectional"))
    )
    (net (code "128") (name "unconnected-(U4-PB12-Pad25)") (class "Default")
      (node (ref "U4") (pin "25") (pinfunction "PB12_25") (pintype "bidirectional"))
    )
    (net (code "129") (name "unconnected-(U4-PB13-Pad26)") (class "Default")
      (node (ref "U4") (pin "26") (pinfunction "PB13_26") (pintype "bidirectional"))
    )
    (net (code "130") (name "unconnected-(U4-PB14-Pad27)") (class "Default")
      (node (ref "U4") (pin "27") (pinfunction "PB14_27") (pintype "bidirectional"))
    )
    (net (code "131") (name "unconnected-(U4-PB15-Pad28)") (class "Default")
      (node (ref "U4") (pin "28") (pinfunction "PB15_28") (pintype "bidirectional"))
    )
    (net (code "132") (name "unconnected-(U4-PC4-Pad16)") (class "Default")
      (node (ref "U4") (pin "16") (pinfunction "PC4_16") (pintype "bidirectional"))
    )
    (net (code "133") (name "unconnected-(U4-PC6-Pad29)") (class "Default")
      (node (ref "U4") (pin "29") (pinfunction "PC6_29") (pintype "bidirectional"))
    )
    (net (code "134") (name "unconnected-(U4-PC10-Pad39)") (class "Default")
      (node (ref "U4") (pin "39") (pinfunction "PC10_39") (pintype "bidirectional"))
    )
    (net (code "135") (name "unconnected-(U4-PC11-Pad40)") (class "Default")
      (node (ref "U4") (pin "40") (pinfunction "PC11_40") (pintype "bidirectional"))
    )
    (net (code "136") (name "unconnected-(U4-PC13-Pad2)") (class "Default")
      (node (ref "U4") (pin "2") (pinfunction "PC13_2") (pintype "bidirectional"))
    )
    (net (code "137") (name "unconnected-(U7-PA0-Pad8)") (class "Default")
      (node (ref "U7") (pin "8") (pinfunction "PA0_8") (pintype "bidirectional"))
    )
    (net (code "138") (name "unconnected-(U7-PA1-Pad9)") (class "Default")
      (node (ref "U7") (pin "9") (pinfunction "PA1_9") (pintype "bidirectional"))
    )
    (net (code "139") (name "unconnected-(U7-PA2-Pad10)") (class "Default")
      (node (ref "U7") (pin "10") (pinfunction "PA2_10") (pintype "bidirectional"))
    )
    (net (code "140") (name "unconnected-(U7-PA3-Pad11)") (class "Default")
      (node (ref "U7") (pin "11") (pinfunction "PA3_11") (pintype "bidirectional"))
    )
    (net (code "141") (name "unconnected-(U7-PA15-Pad38)") (class "Default")
      (node (ref "U7") (pin "38") (pinfunction "PA15_38") (pintype "bidirectional"))
    )
    (net (code "142") (name "unconnected-(U7-PB3-Pad41)") (class "Default")
      (node (ref "U7") (pin "41") (pinfunction "PB3_41") (pintype "bidirectional"))
    )
    (net (code "143") (name "unconnected-(U7-PB4-Pad42)") (class "Default")
      (node (ref "U7") (pin "42") (pinfunction "PB4_42") (pintype "bidirectional"))
    )
    (net (code "144") (name "unconnected-(U7-PB5-Pad43)") (class "Default")
      (node (ref "U7") (pin "43") (pinfunction "PB5_43") (pintype "bidirectional"))
    )
    (net (code "145") (name "unconnected-(U7-PB6-Pad44)") (class "Default")
      (node (ref "U7") (pin "44") (pinfunction "PB6_44") (pintype "bidirectional"))
    )
    (net (code "146") (name "unconnected-(U7-PB7-Pad45)") (class "Default")
      (node (ref "U7") (pin "45") (pinfunction "PB7_45") (pintype "bidirectional"))
    )
    (net (code "147") (name "unconnected-(U7-PB8-BOOT0-Pad46)") (class "Default")
      (node (ref "U7") (pin "46") (pinfunction "PB8-BOOT0_46") (pintype "bidirectional"))
    )
    (net (code "148") (name "unconnected-(U7-PB9-Pad47)") (class "Default")
      (node (ref "U7") (pin "47") (pinfunction "PB9_47") (pintype "bidirectional"))
    )
    (net (code "149") (name "unconnected-(U7-PC6-Pad29)") (class "Default")
      (node (ref "U7") (pin "29") (pinfunction "PC6_29") (pintype "bidirectional"))
    )
    (net (code "150") (name "unconnected-(U7-PC10-Pad39)") (class "Default")
      (node (ref "U7") (pin "39") (pinfunction "PC10_39") (pintype "bidirectional"))
    )
    (net (code "151") (name "unconnected-(U7-PC11-Pad40)") (class "Default")
      (node (ref "U7") (pin "40") (pinfunction "PC11_40") (pintype "bidirectional"))
    )
    (net (code "152") (name "unconnected-(U7-PC13-Pad2)") (class "Default")
      (node (ref "U7") (pin "2") (pinfunction "PC13_2") (pintype "bidirectional"))
    )
    (net (code "153") (name "unconnected-(U8-INT2-Pad1)") (class "Default")
      (node (ref "U8") (pin "1") (pinfunction "INT2_1") (pintype "bidirectional"))
    )
    (net (code "154") (name "unconnected-(U8-INT4-Pad13)") (class "Default")
      (node (ref "U8") (pin "13") (pinfunction "INT4_13") (pintype "bidirectional"))
    )
    (net (code "155") (name "unconnected-(U8-NC-Pad2)") (class "Default")
      (node (ref "U8") (pin "2") (pinfunction "NC_2") (pintype "bidirectional"))
    )
    (net (code "156") (name "unconnected-(U11-PA0-Pad8)") (class "Default")
      (node (ref "U11") (pin "8") (pinfunction "PA0_8") (pintype "bidirectional"))
    )
    (net (code "157") (name "unconnected-(U11-PA1-Pad9)") (class "Default")
      (node (ref "U11") (pin "9") (pinfunction "PA1_9") (pintype "bidirectional"))
    )
    (net (code "158") (name "unconnected-(U11-PA2-Pad10)") (class "Default")
      (node (ref "U11") (pin "10") (pinfunction "PA2_10") (pintype "bidirectional"))
    )
    (net (code "159") (name "unconnected-(U11-PA3-Pad11)") (class "Default")
      (node (ref "U11") (pin "11") (pinfunction "PA3_11") (pintype "bidirectional"))
    )
    (net (code "160") (name "unconnected-(U11-PA8-Pad30)") (class "Default")
      (node (ref "U11") (pin "30") (pinfunction "PA8_30") (pintype "bidirectional"))
    )
    (net (code "161") (name "unconnected-(U11-PA9-Pad31)") (class "Default")
      (node (ref "U11") (pin "31") (pinfunction "PA9_31") (pintype "bidirectional"))
    )
    (net (code "162") (name "unconnected-(U11-PA10-Pad32)") (class "Default")
      (node (ref "U11") (pin "32") (pinfunction "PA10_32") (pintype "bidirectional"))
    )
    (net (code "163") (name "unconnected-(U11-PA15-Pad38)") (class "Default")
      (node (ref "U11") (pin "38") (pinfunction "PA15_38") (pintype "bidirectional"))
    )
    (net (code "164") (name "unconnected-(U11-PB1-Pad18)") (class "Default")
      (node (ref "U11") (pin "18") (pinfunction "PB1_18") (pintype "bidirectional"))
    )
    (net (code "165") (name "unconnected-(U11-PB2-Pad19)") (class "Default")
      (node (ref "U11") (pin "19") (pinfunction "PB2_19") (pintype "bidirectional"))
    )
    (net (code "166") (name "unconnected-(U11-PB5-Pad43)") (class "Default")
      (node (ref "U11") (pin "43") (pinfunction "PB5_43") (pintype "bidirectional"))
    )
    (net (code "167") (name "unconnected-(U11-PB6-Pad44)") (class "Default")
      (node (ref "U11") (pin "44") (pinfunction "PB6_44") (pintype "bidirectional"))
    )
    (net (code "168") (name "unconnected-(U11-PB7-Pad45)") (class "Default")
      (node (ref "U11") (pin "45") (pinfunction "PB7_45") (pintype "bidirectional"))
    )
    (net (code "169") (name "unconnected-(U11-PB8-BOOT0-Pad46)") (class "Default")
      (node (ref "U11") (pin "46") (pinfunction "PB8-BOOT0_46") (pintype "bidirectional"))
    )
    (net (code "170") (name "unconnected-(U11-PB9-Pad47)") (class "Default")
      (node (ref "U11") (pin "47") (pinfunction "PB9_47") (pintype "bidirectional"))
    )
    (net (code "171") (name "unconnected-(U11-PB10-Pad22)") (class "Default")
      (node (ref "U11") (pin "22") (pinfunction "PB10_22") (pintype "bidirectional"))
    )
    (net (code "172") (name "unconnected-(U11-PB11-Pad24)") (class "Default")
      (node (ref "U11") (pin "24") (pinfunction "PB11_24") (pintype "bidirectional"))
    )
    (net (code "173") (name "unconnected-(U11-PB12-Pad25)") (class "Default")
      (node (ref "U11") (pin "25") (pinfunction "PB12_25") (pintype "bidirectional"))
    )
    (net (code "174") (name "unconnected-(U11-PB13-Pad26)") (class "Default")
      (node (ref "U11") (pin "26") (pinfunction "PB13_26") (pintype "bidirectional"))
    )
    (net (code "175") (name "unconnected-(U11-PB14-Pad27)") (class "Default")
      (node (ref "U11") (pin "27") (pinfunction "PB14_27") (pintype "bidirectional"))
    )
    (net (code "176") (name "unconnected-(U11-PB15-Pad28)") (class "Default")
      (node (ref "U11") (pin "28") (pinfunction "PB15_28") (pintype "bidirectional"))
    )
    (net (code "177") (name "unconnected-(U11-PC4-Pad16)") (class "Default")
      (node (ref "U11") (pin "16") (pinfunction "PC4_16") (pintype "bidirectional"))
    )
    (net (code "178") (name "unconnected-(U11-PC6-Pad29)") (class "Default")
      (node (ref "U11") (pin "29") (pinfunction "PC6_29") (pintype "bidirectional"))
    )
    (net (code "179") (name "unconnected-(U11-PC10-Pad39)") (class "Default")
      (node (ref "U11") (pin "39") (pinfunction "PC10_39") (pintype "bidirectional"))
    )
    (net (code "180") (name "unconnected-(U11-PC11-Pad40)") (class "Default")
      (node (ref "U11") (pin "40") (pinfunction "PC11_40") (pintype "bidirectional"))
    )
    (net (code "181") (name "unconnected-(U11-PC13-Pad2)") (class "Default")
      (node (ref "U11") (pin "2") (pinfunction "PC13_2") (pintype "bidirectional"))
    )
    (net (code "182") (name "unconnected-(U14-RESV_2-Pad2)") (class "Default")
      (node (ref "U14") (pin "2") (pinfunction "RESV_2_2") (pintype "passive"))
    )
    (net (code "183") (name "unconnected-(U14-RESV_3-Pad3)") (class "Default")
      (node (ref "U14") (pin "3") (pinfunction "RESV_3_3") (pintype "passive"))
    )
    (net (code "184") (name "unconnected-(U14-RESV_7-Pad7)") (class "Default")
      (node (ref "U14") (pin "7") (pinfunction "RESV_7_7") (pintype "passive"))
    )
    (net (code "185") (name "unconnected-(U14-RESV_10-Pad10)") (class "Default")
      (node (ref "U14") (pin "10") (pinfunction "RESV_10_10") (pintype "passive"))
    )
    (net (code "186") (name "unconnected-(U14-RESV_11-Pad11)") (class "Default")
      (node (ref "U14") (pin "11") (pinfunction "RESV_11_11") (pintype "passive"))
    )
  )
)
